# EMG_SS19_Version.net
KiCad netlist of a schematic drawn in EAGLE
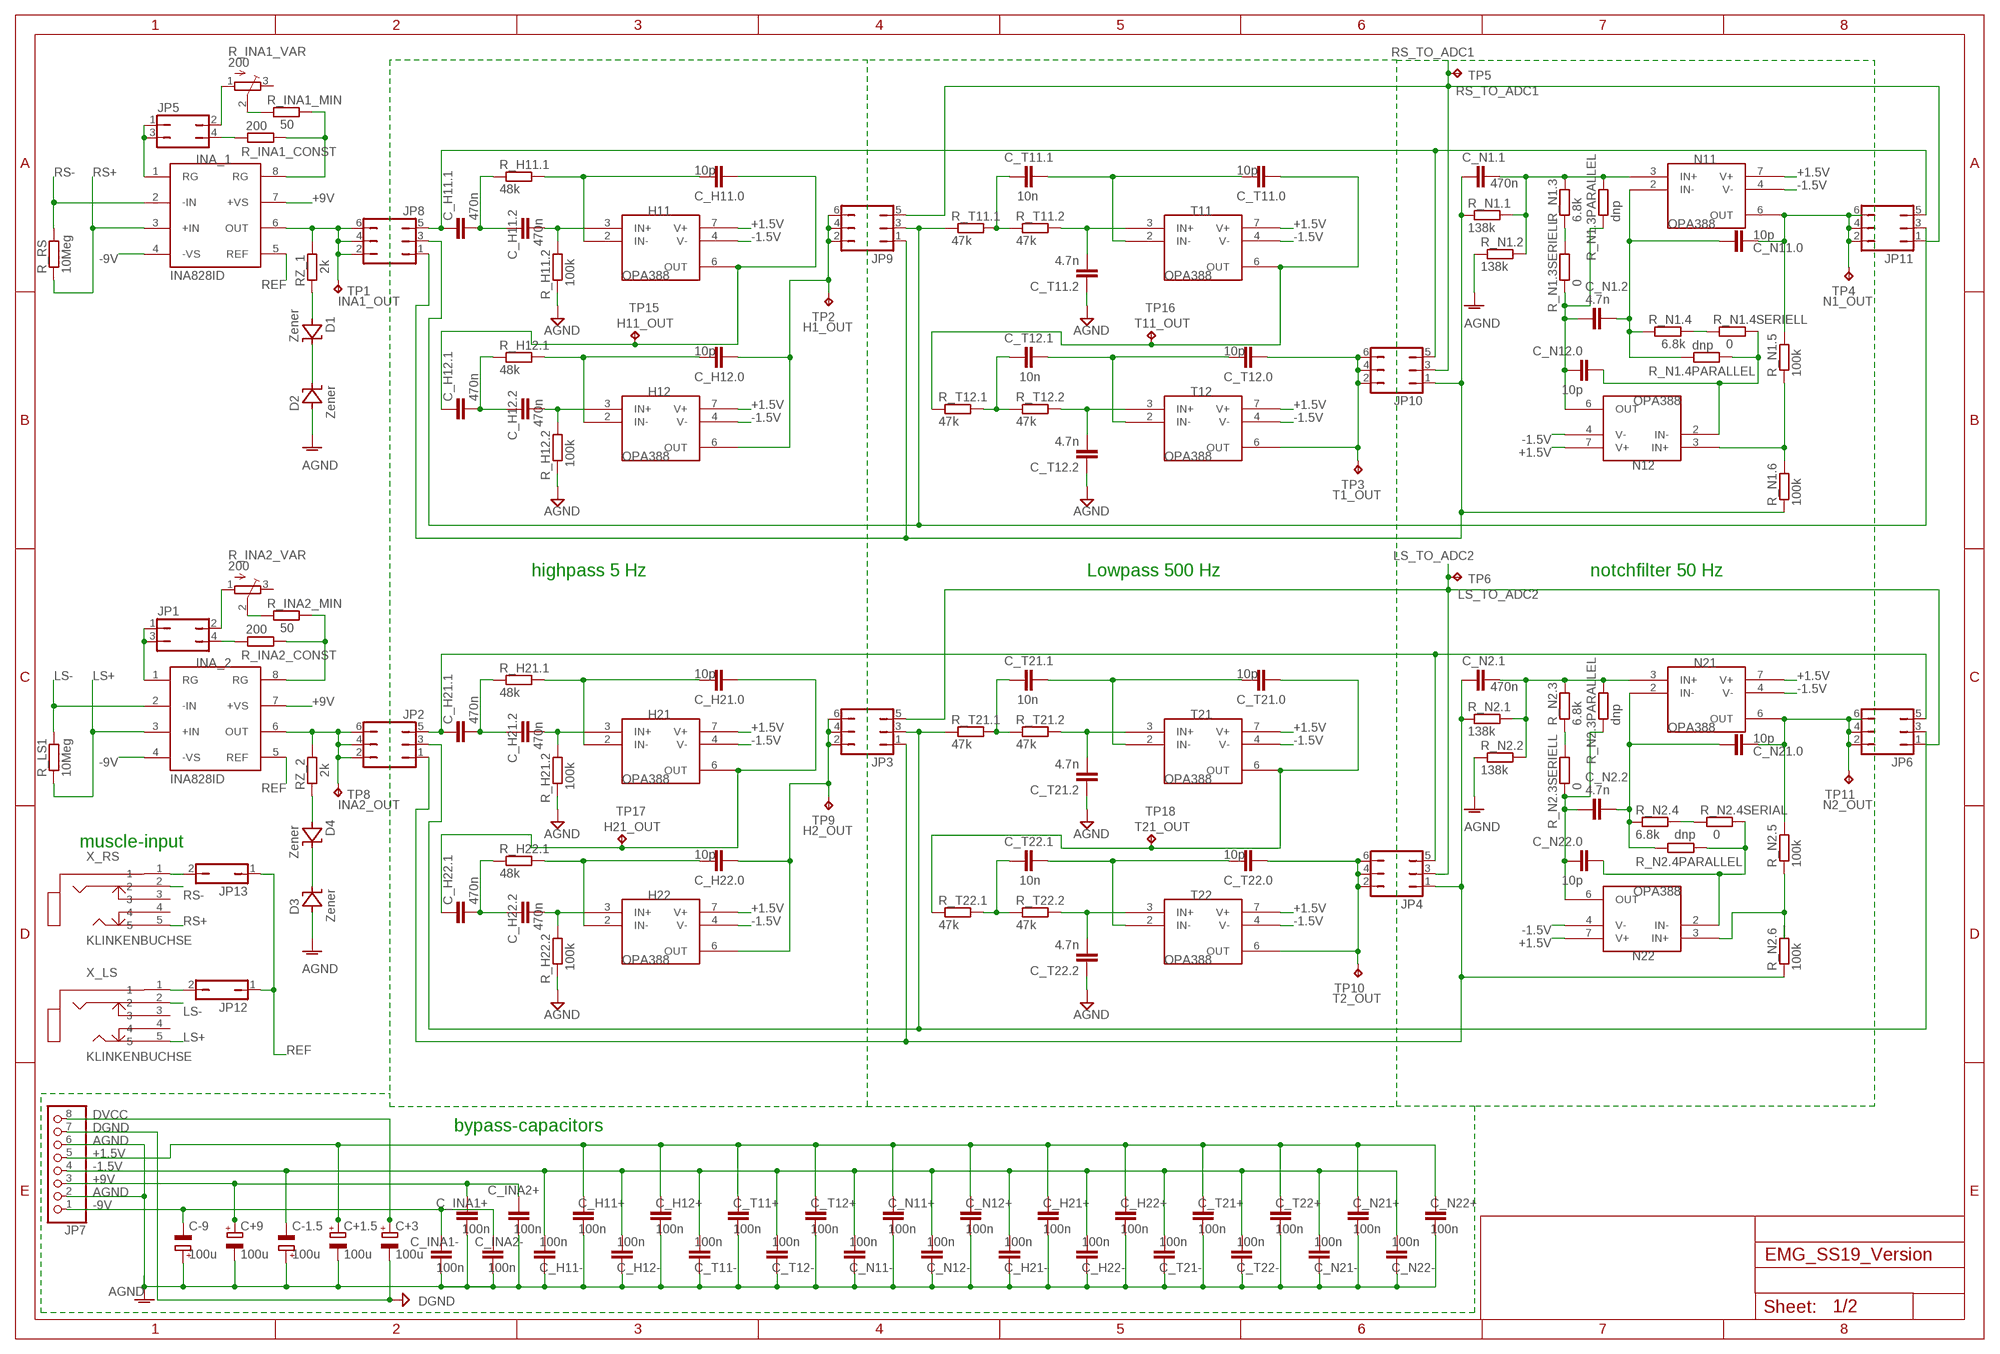
[diagram p0: schematic, sheet 1]
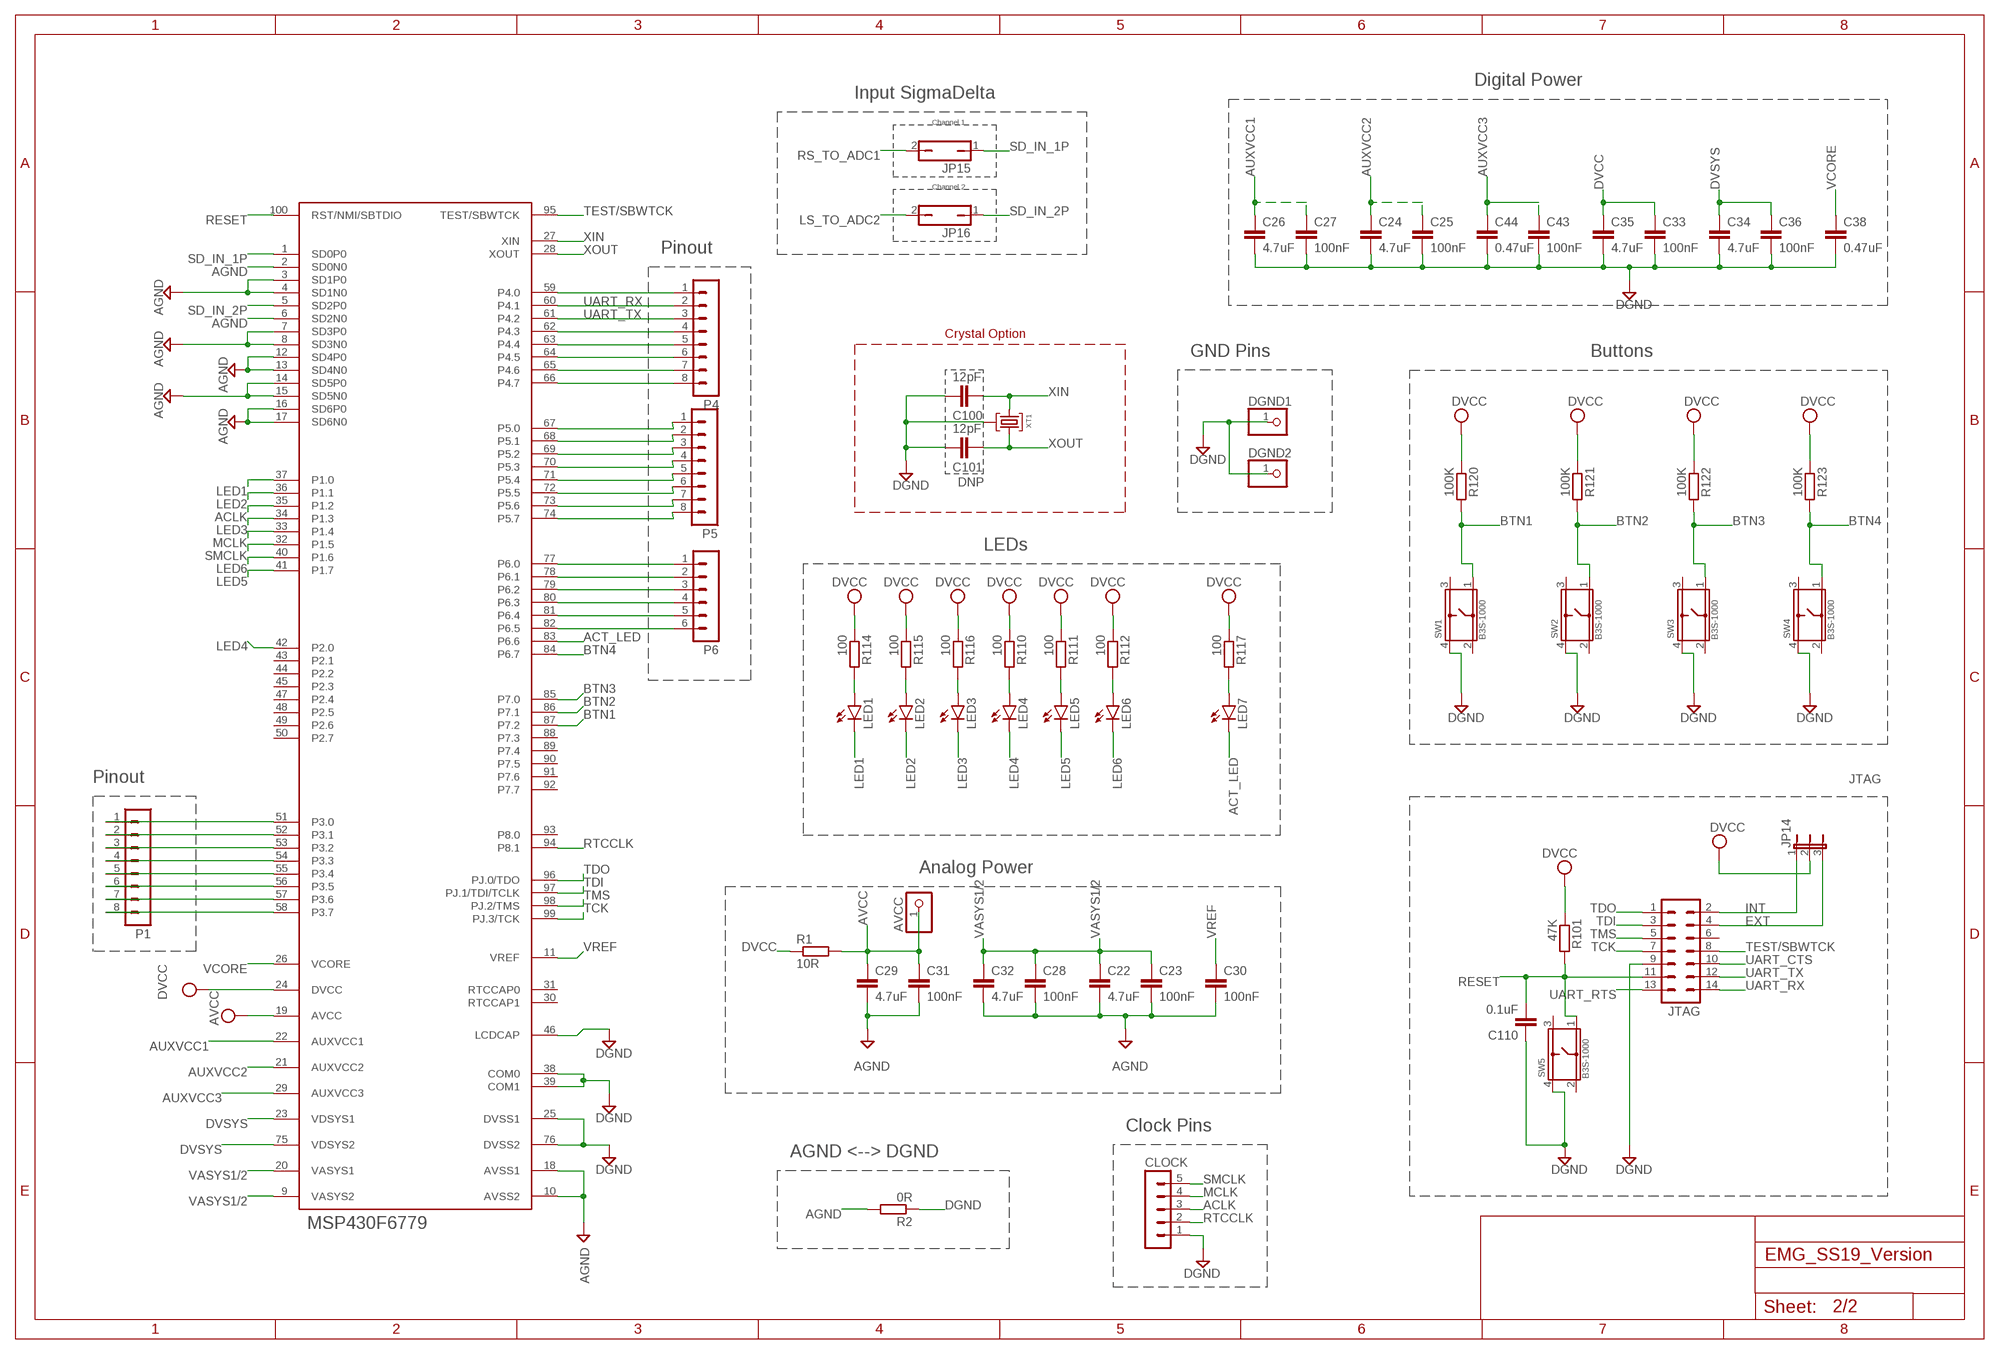
[diagram p1: schematic, sheet 2]

(export (version "E")
  (design (tool "Eeschema 10.0.6"))
  (components
    (comp (ref "C+1.5")
      (value "100u")
      (footprint "eagle-import:RADIAL_SMD_ELKO_6_3")
      (fields (field (name "MF") "Wurth Electronics") (field (name "MP") "865080545012"))
      (libsource (lib "eagle-import") (part "ELKO_SMD"))
    )
    (comp (ref "C+3")
      (value "100u")
      (footprint "eagle-import:RADIAL_SMD_ELKO_6_3")
      (fields (field (name "MF") "Wurth Electronics") (field (name "MP") "865080545012"))
      (libsource (lib "eagle-import") (part "ELKO_SMD"))
    )
    (comp (ref "C+9")
      (value "100u")
      (footprint "eagle-import:RADIAL_SMD_ELKO_6_3")
      (fields (field (name "MF") "Wurth Electronics") (field (name "MP") "865080545012"))
      (libsource (lib "eagle-import") (part "ELKO_SMD"))
    )
    (comp (ref "C-1.5")
      (value "100u")
      (footprint "eagle-import:RADIAL_SMD_ELKO_6_3")
      (fields (field (name "MF") "Wurth Electronics") (field (name "MP") "865080545012"))
      (libsource (lib "eagle-import") (part "ELKO_SMD"))
    )
    (comp (ref "C-9")
      (value "100u")
      (footprint "eagle-import:RADIAL_SMD_ELKO_6_3")
      (fields (field (name "MF") "Wurth Electronics") (field (name "MP") "865080545012"))
      (libsource (lib "eagle-import") (part "ELKO_SMD"))
    )
    (comp (ref "C_H11+")
      (value "100n")
      (footprint "eagle-import:C0805")
      (libsource (lib "eagle-import") (part "C-EUC0805"))
    )
    (comp (ref "C_H11-")
      (value "100n")
      (footprint "eagle-import:C0805")
      (libsource (lib "eagle-import") (part "C-EUC0805"))
    )
    (comp (ref "C_H11.0")
      (value "10p")
      (footprint "eagle-import:C0805")
      (libsource (lib "eagle-import") (part "C-EUC0805"))
    )
    (comp (ref "C_H11.1")
      (value "470n")
      (footprint "eagle-import:C0805")
      (libsource (lib "eagle-import") (part "C-EUC0805"))
    )
    (comp (ref "C_H11.2")
      (value "470n")
      (footprint "eagle-import:C0805")
      (libsource (lib "eagle-import") (part "C-EUC0805"))
    )
    (comp (ref "C_H12+")
      (value "100n")
      (footprint "eagle-import:C0805")
      (libsource (lib "eagle-import") (part "C-EUC0805"))
    )
    (comp (ref "C_H12-")
      (value "100n")
      (footprint "eagle-import:C0805")
      (libsource (lib "eagle-import") (part "C-EUC0805"))
    )
    (comp (ref "C_H12.0")
      (value "10p")
      (footprint "eagle-import:C0805")
      (libsource (lib "eagle-import") (part "C-EUC0805"))
    )
    (comp (ref "C_H12.1")
      (value "470n")
      (footprint "eagle-import:C0805")
      (libsource (lib "eagle-import") (part "C-EUC0805"))
    )
    (comp (ref "C_H12.2")
      (value "470n")
      (footprint "eagle-import:C0805")
      (libsource (lib "eagle-import") (part "C-EUC0805"))
    )
    (comp (ref "C_H21+")
      (value "100n")
      (footprint "eagle-import:C0805")
      (libsource (lib "eagle-import") (part "C-EUC0805"))
    )
    (comp (ref "C_H21-")
      (value "100n")
      (footprint "eagle-import:C0805")
      (libsource (lib "eagle-import") (part "C-EUC0805"))
    )
    (comp (ref "C_H21.0")
      (value "10p")
      (footprint "eagle-import:C0805")
      (libsource (lib "eagle-import") (part "C-EUC0805"))
    )
    (comp (ref "C_H21.1")
      (value "470n")
      (footprint "eagle-import:C0805")
      (libsource (lib "eagle-import") (part "C-EUC0805"))
    )
    (comp (ref "C_H21.2")
      (value "470n")
      (footprint "eagle-import:C0805")
      (libsource (lib "eagle-import") (part "C-EUC0805"))
    )
    (comp (ref "C_H22+")
      (value "100n")
      (footprint "eagle-import:C0805")
      (libsource (lib "eagle-import") (part "C-EUC0805"))
    )
    (comp (ref "C_H22-")
      (value "100n")
      (footprint "eagle-import:C0805")
      (libsource (lib "eagle-import") (part "C-EUC0805"))
    )
    (comp (ref "C_H22.0")
      (value "10p")
      (footprint "eagle-import:C0805")
      (libsource (lib "eagle-import") (part "C-EUC0805"))
    )
    (comp (ref "C_H22.1")
      (value "470n")
      (footprint "eagle-import:C0805")
      (libsource (lib "eagle-import") (part "C-EUC0805"))
    )
    (comp (ref "C_H22.2")
      (value "470n")
      (footprint "eagle-import:C0805")
      (libsource (lib "eagle-import") (part "C-EUC0805"))
    )
    (comp (ref "C_INA1+")
      (value "100n")
      (footprint "eagle-import:C0805")
      (libsource (lib "eagle-import") (part "C-EUC0805"))
    )
    (comp (ref "C_INA1-")
      (value "100n")
      (footprint "eagle-import:C0805")
      (libsource (lib "eagle-import") (part "C-EUC0805"))
    )
    (comp (ref "C_INA2+")
      (value "100n")
      (footprint "eagle-import:C0805")
      (libsource (lib "eagle-import") (part "C-EUC0805"))
    )
    (comp (ref "C_INA2-")
      (value "100n")
      (footprint "eagle-import:C0805")
      (libsource (lib "eagle-import") (part "C-EUC0805"))
    )
    (comp (ref "C_N1.1")
      (value "470n")
      (footprint "eagle-import:C0805")
      (libsource (lib "eagle-import") (part "C-EUC0805"))
    )
    (comp (ref "C_N1.2")
      (value "4.7n")
      (footprint "eagle-import:C0805")
      (libsource (lib "eagle-import") (part "C-EUC0805"))
    )
    (comp (ref "C_N2.1")
      (value "470n")
      (footprint "eagle-import:C0805")
      (libsource (lib "eagle-import") (part "C-EUC0805"))
    )
    (comp (ref "C_N2.2")
      (value "4.7n")
      (footprint "eagle-import:C0805")
      (libsource (lib "eagle-import") (part "C-EUC0805"))
    )
    (comp (ref "C_N11+")
      (value "100n")
      (footprint "eagle-import:C0805")
      (libsource (lib "eagle-import") (part "C-EUC0805"))
    )
    (comp (ref "C_N11-")
      (value "100n")
      (footprint "eagle-import:C0805")
      (libsource (lib "eagle-import") (part "C-EUC0805"))
    )
    (comp (ref "C_N11.0")
      (value "10p")
      (footprint "eagle-import:C0805")
      (libsource (lib "eagle-import") (part "C-EUC0805"))
    )
    (comp (ref "C_N12+")
      (value "100n")
      (footprint "eagle-import:C0805")
      (libsource (lib "eagle-import") (part "C-EUC0805"))
    )
    (comp (ref "C_N12-")
      (value "100n")
      (footprint "eagle-import:C0805")
      (libsource (lib "eagle-import") (part "C-EUC0805"))
    )
    (comp (ref "C_N12.0")
      (value "10p")
      (footprint "eagle-import:C0805")
      (libsource (lib "eagle-import") (part "C-EUC0805"))
    )
    (comp (ref "C_N21+")
      (value "100n")
      (footprint "eagle-import:C0805")
      (libsource (lib "eagle-import") (part "C-EUC0805"))
    )
    (comp (ref "C_N21-")
      (value "100n")
      (footprint "eagle-import:C0805")
      (libsource (lib "eagle-import") (part "C-EUC0805"))
    )
    (comp (ref "C_N21.0")
      (value "10p")
      (footprint "eagle-import:C0805")
      (libsource (lib "eagle-import") (part "C-EUC0805"))
    )
    (comp (ref "C_N22+")
      (value "100n")
      (footprint "eagle-import:C0805")
      (libsource (lib "eagle-import") (part "C-EUC0805"))
    )
    (comp (ref "C_N22-")
      (value "100n")
      (footprint "eagle-import:C0805")
      (libsource (lib "eagle-import") (part "C-EUC0805"))
    )
    (comp (ref "C_N22.0")
      (value "10p")
      (footprint "eagle-import:C0805")
      (libsource (lib "eagle-import") (part "C-EUC0805"))
    )
    (comp (ref "C_T11+")
      (value "100n")
      (footprint "eagle-import:C0805")
      (libsource (lib "eagle-import") (part "C-EUC0805"))
    )
    (comp (ref "C_T11-")
      (value "100n")
      (footprint "eagle-import:C0805")
      (libsource (lib "eagle-import") (part "C-EUC0805"))
    )
    (comp (ref "C_T11.0")
      (value "10p")
      (footprint "eagle-import:C0805")
      (libsource (lib "eagle-import") (part "C-EUC0805"))
    )
    (comp (ref "C_T11.1")
      (value "10n")
      (footprint "eagle-import:C0805")
      (libsource (lib "eagle-import") (part "C-EUC0805"))
    )
    (comp (ref "C_T11.2")
      (value "4.7n")
      (footprint "eagle-import:C0805")
      (libsource (lib "eagle-import") (part "C-EUC0805"))
    )
    (comp (ref "C_T12+")
      (value "100n")
      (footprint "eagle-import:C0805")
      (libsource (lib "eagle-import") (part "C-EUC0805"))
    )
    (comp (ref "C_T12-")
      (value "100n")
      (footprint "eagle-import:C0805")
      (libsource (lib "eagle-import") (part "C-EUC0805"))
    )
    (comp (ref "C_T12.0")
      (value "10p")
      (footprint "eagle-import:C0805")
      (libsource (lib "eagle-import") (part "C-EUC0805"))
    )
    (comp (ref "C_T12.1")
      (value "10n")
      (footprint "eagle-import:C0805")
      (libsource (lib "eagle-import") (part "C-EUC0805"))
    )
    (comp (ref "C_T12.2")
      (value "4.7n")
      (footprint "eagle-import:C0805")
      (libsource (lib "eagle-import") (part "C-EUC0805"))
    )
    (comp (ref "C_T21+")
      (value "100n")
      (footprint "eagle-import:C0805")
      (libsource (lib "eagle-import") (part "C-EUC0805"))
    )
    (comp (ref "C_T21-")
      (value "100n")
      (footprint "eagle-import:C0805")
      (libsource (lib "eagle-import") (part "C-EUC0805"))
    )
    (comp (ref "C_T21.0")
      (value "10p")
      (footprint "eagle-import:C0805")
      (libsource (lib "eagle-import") (part "C-EUC0805"))
    )
    (comp (ref "C_T21.1")
      (value "10n")
      (footprint "eagle-import:C0805")
      (libsource (lib "eagle-import") (part "C-EUC0805"))
    )
    (comp (ref "C_T21.2")
      (value "4.7n")
      (footprint "eagle-import:C0805")
      (libsource (lib "eagle-import") (part "C-EUC0805"))
    )
    (comp (ref "C_T22+")
      (value "100n")
      (footprint "eagle-import:C0805")
      (libsource (lib "eagle-import") (part "C-EUC0805"))
    )
    (comp (ref "C_T22-")
      (value "100n")
      (footprint "eagle-import:C0805")
      (libsource (lib "eagle-import") (part "C-EUC0805"))
    )
    (comp (ref "C_T22.0")
      (value "10p")
      (footprint "eagle-import:C0805")
      (libsource (lib "eagle-import") (part "C-EUC0805"))
    )
    (comp (ref "C_T22.1")
      (value "10n")
      (footprint "eagle-import:C0805")
      (libsource (lib "eagle-import") (part "C-EUC0805"))
    )
    (comp (ref "C_T22.2")
      (value "4.7n")
      (footprint "eagle-import:C0805")
      (libsource (lib "eagle-import") (part "C-EUC0805"))
    )
    (comp (ref "D1")
      (value "Zener")
      (footprint "eagle-import:SOT-23")
      (fields (field (name "MF") "Diodes Inc.") (field (name "MP") "ZXCT1109SA-7"))
      (libsource (lib "eagle-import") (part "ZENER_SMD_ZD_8.2"))
    )
    (comp (ref "D2")
      (value "Zener")
      (footprint "eagle-import:SOT-23")
      (fields (field (name "MF") "Diodes Inc.") (field (name "MP") "ZXCT1109SA-7"))
      (libsource (lib "eagle-import") (part "ZENER_SMD_ZD_8.2"))
    )
    (comp (ref "D3")
      (value "Zener")
      (footprint "eagle-import:SOT-23")
      (fields (field (name "MF") "Diodes Inc.") (field (name "MP") "ZXCT1109SA-7"))
      (libsource (lib "eagle-import") (part "ZENER_SMD_ZD_8.2"))
    )
    (comp (ref "D4")
      (value "Zener")
      (footprint "eagle-import:SOT-23")
      (fields (field (name "MF") "Diodes Inc.") (field (name "MP") "ZXCT1109SA-7"))
      (libsource (lib "eagle-import") (part "ZENER_SMD_ZD_8.2"))
    )
    (comp (ref "H11")
      (value "OPA388")
      (footprint "eagle-import:SOIC127P600X175-8N")
      (libsource (lib "eagle-import") (part "OPA388"))
    )
    (comp (ref "H12")
      (value "OPA388")
      (footprint "eagle-import:SOIC127P600X175-8N")
      (libsource (lib "eagle-import") (part "OPA388"))
    )
    (comp (ref "H21")
      (value "OPA388")
      (footprint "eagle-import:SOIC127P600X175-8N")
      (libsource (lib "eagle-import") (part "OPA388"))
    )
    (comp (ref "H22")
      (value "OPA388")
      (footprint "eagle-import:SOIC127P600X175-8N")
      (libsource (lib "eagle-import") (part "OPA388"))
    )
    (comp (ref "INA_1")
      (value "INA828ID")
      (footprint "eagle-import:SOIC8")
      (fields (field (name "DIGI-KEY_PART_NUMBER") "296-47415-ND") (field (name "MF") "Texas Instruments"))
      (libsource (lib "eagle-import") (part "INA828ID"))
    )
    (comp (ref "INA_2")
      (value "INA828ID")
      (footprint "eagle-import:SOIC8")
      (fields (field (name "DIGI-KEY_PART_NUMBER") "296-47415-ND") (field (name "MF") "Texas Instruments"))
      (libsource (lib "eagle-import") (part "INA828ID"))
    )
    (comp (ref "JP1")
      (value "JP2Q")
      (footprint "eagle-import:JP2Q")
      (libsource (lib "eagle-import") (part "JP2Q"))
    )
    (comp (ref "JP2")
      (value "JP3Q")
      (footprint "eagle-import:JP3Q")
      (libsource (lib "eagle-import") (part "JP3Q"))
    )
    (comp (ref "JP3")
      (value "JP3Q")
      (footprint "eagle-import:JP3Q")
      (libsource (lib "eagle-import") (part "JP3Q"))
    )
    (comp (ref "JP4")
      (value "JP3Q")
      (footprint "eagle-import:JP3Q")
      (libsource (lib "eagle-import") (part "JP3Q"))
    )
    (comp (ref "JP5")
      (value "JP2Q")
      (footprint "eagle-import:JP2Q")
      (libsource (lib "eagle-import") (part "JP2Q"))
    )
    (comp (ref "JP6")
      (value "JP3Q")
      (footprint "eagle-import:JP3Q")
      (libsource (lib "eagle-import") (part "JP3Q"))
    )
    (comp (ref "JP7")
      (value "PINHD-1X8")
      (footprint "eagle-import:1X08")
      (libsource (lib "eagle-import") (part "PINHD-1X8"))
    )
    (comp (ref "JP8")
      (value "JP3Q")
      (footprint "eagle-import:JP3Q")
      (libsource (lib "eagle-import") (part "JP3Q"))
    )
    (comp (ref "JP9")
      (value "JP3Q")
      (footprint "eagle-import:JP3Q")
      (libsource (lib "eagle-import") (part "JP3Q"))
    )
    (comp (ref "JP10")
      (value "JP3Q")
      (footprint "eagle-import:JP3Q")
      (libsource (lib "eagle-import") (part "JP3Q"))
    )
    (comp (ref "JP11")
      (value "JP3Q")
      (footprint "eagle-import:JP3Q")
      (libsource (lib "eagle-import") (part "JP3Q"))
    )
    (comp (ref "JP12")
      (value "JP1Q")
      (footprint "eagle-import:JP1")
      (libsource (lib "eagle-import") (part "JP1Q"))
    )
    (comp (ref "JP13")
      (value "JP1Q")
      (footprint "eagle-import:JP1")
      (libsource (lib "eagle-import") (part "JP1Q"))
    )
    (comp (ref "N11")
      (value "OPA388")
      (footprint "eagle-import:SOIC127P600X175-8N")
      (libsource (lib "eagle-import") (part "OPA388"))
    )
    (comp (ref "N12")
      (value "OPA388")
      (footprint "eagle-import:SOIC127P600X175-8N")
      (libsource (lib "eagle-import") (part "OPA388"))
    )
    (comp (ref "N21")
      (value "OPA388")
      (footprint "eagle-import:SOIC127P600X175-8N")
      (libsource (lib "eagle-import") (part "OPA388"))
    )
    (comp (ref "N22")
      (value "OPA388")
      (footprint "eagle-import:SOIC127P600X175-8N")
      (libsource (lib "eagle-import") (part "OPA388"))
    )
    (comp (ref "RZ_1")
      (value "2k")
      (footprint "eagle-import:R0805")
      (libsource (lib "eagle-import") (part "R-EU_R0805"))
    )
    (comp (ref "RZ_2")
      (value "2k")
      (footprint "eagle-import:R0805")
      (libsource (lib "eagle-import") (part "R-EU_R0805"))
    )
    (comp (ref "R_H11.1")
      (value "48k")
      (footprint "eagle-import:R0805")
      (libsource (lib "eagle-import") (part "R-EU_R0805"))
    )
    (comp (ref "R_H11.2")
      (value "100k")
      (footprint "eagle-import:R0805")
      (libsource (lib "eagle-import") (part "R-EU_R0805"))
    )
    (comp (ref "R_H12.1")
      (value "48k")
      (footprint "eagle-import:R0805")
      (libsource (lib "eagle-import") (part "R-EU_R0805"))
    )
    (comp (ref "R_H12.2")
      (value "100k")
      (footprint "eagle-import:R0805")
      (libsource (lib "eagle-import") (part "R-EU_R0805"))
    )
    (comp (ref "R_H21.1")
      (value "48k")
      (footprint "eagle-import:R0805")
      (libsource (lib "eagle-import") (part "R-EU_R0805"))
    )
    (comp (ref "R_H21.2")
      (value "100k")
      (footprint "eagle-import:R0805")
      (libsource (lib "eagle-import") (part "R-EU_R0805"))
    )
    (comp (ref "R_H22.1")
      (value "48k")
      (footprint "eagle-import:R0805")
      (libsource (lib "eagle-import") (part "R-EU_R0805"))
    )
    (comp (ref "R_H22.2")
      (value "100k")
      (footprint "eagle-import:R0805")
      (libsource (lib "eagle-import") (part "R-EU_R0805"))
    )
    (comp (ref "R_INA1_CONST")
      (value "200")
      (footprint "eagle-import:R0805")
      (libsource (lib "eagle-import") (part "R-EU_R0805"))
    )
    (comp (ref "R_INA1_MIN")
      (value "50")
      (footprint "eagle-import:R0805")
      (libsource (lib "eagle-import") (part "R-EU_R0805"))
    )
    (comp (ref "R_INA1_VAR")
      (value "200")
      (footprint "eagle-import:SM-42_43W")
      (fields (field (name "SPICEPREFIX") "J"))
      (libsource (lib "eagle-import") (part "TRIM_EU-SM-42/43W"))
    )
    (comp (ref "R_INA2_CONST")
      (value "200")
      (footprint "eagle-import:R0805")
      (libsource (lib "eagle-import") (part "R-EU_R0805"))
    )
    (comp (ref "R_INA2_MIN")
      (value "50")
      (footprint "eagle-import:R0805")
      (libsource (lib "eagle-import") (part "R-EU_R0805"))
    )
    (comp (ref "R_INA2_VAR")
      (value "200")
      (footprint "eagle-import:SM-42_43W")
      (fields (field (name "SPICEPREFIX") "J"))
      (libsource (lib "eagle-import") (part "TRIM_EU-SM-42/43W"))
    )
    (comp (ref "R_LS1")
      (value "10Meg")
      (footprint "eagle-import:R0805")
      (libsource (lib "eagle-import") (part "R-EU_R0805"))
    )
    (comp (ref "R_N1.1")
      (value "138k")
      (footprint "eagle-import:R0805")
      (libsource (lib "eagle-import") (part "R-EU_R0805"))
    )
    (comp (ref "R_N1.2")
      (value "138k")
      (footprint "eagle-import:R0805")
      (libsource (lib "eagle-import") (part "R-EU_R0805"))
    )
    (comp (ref "R_N1.3")
      (value "6.8k")
      (footprint "eagle-import:R0805")
      (libsource (lib "eagle-import") (part "R-EU_R0805"))
    )
    (comp (ref "R_N1.3PARALLEL")
      (value "dnp")
      (footprint "eagle-import:R0805")
      (libsource (lib "eagle-import") (part "R-EU_R0805"))
    )
    (comp (ref "R_N1.3SERIELL")
      (value "0")
      (footprint "eagle-import:R0805")
      (libsource (lib "eagle-import") (part "R-EU_R0805"))
    )
    (comp (ref "R_N1.4")
      (value "6.8k")
      (footprint "eagle-import:R0805")
      (libsource (lib "eagle-import") (part "R-EU_R0805"))
    )
    (comp (ref "R_N1.4PARALLEL")
      (value "dnp")
      (footprint "eagle-import:R0805")
      (libsource (lib "eagle-import") (part "R-EU_R0805"))
    )
    (comp (ref "R_N1.4SERIELL")
      (value "0")
      (footprint "eagle-import:R0805")
      (libsource (lib "eagle-import") (part "R-EU_R0805"))
    )
    (comp (ref "R_N1.5")
      (value "100k")
      (footprint "eagle-import:R0805")
      (libsource (lib "eagle-import") (part "R-EU_R0805"))
    )
    (comp (ref "R_N1.6")
      (value "100k")
      (footprint "eagle-import:R0805")
      (libsource (lib "eagle-import") (part "R-EU_R0805"))
    )
    (comp (ref "R_N2.1")
      (value "138k")
      (footprint "eagle-import:R0805")
      (libsource (lib "eagle-import") (part "R-EU_R0805"))
    )
    (comp (ref "R_N2.2")
      (value "138k")
      (footprint "eagle-import:R0805")
      (libsource (lib "eagle-import") (part "R-EU_R0805"))
    )
    (comp (ref "R_N2.3")
      (value "6.8k")
      (footprint "eagle-import:R0805")
      (libsource (lib "eagle-import") (part "R-EU_R0805"))
    )
    (comp (ref "R_N2.3PARALLEL")
      (value "dnp")
      (footprint "eagle-import:R0805")
      (libsource (lib "eagle-import") (part "R-EU_R0805"))
    )
    (comp (ref "R_N2.3SERIELL")
      (value "0")
      (footprint "eagle-import:R0805")
      (libsource (lib "eagle-import") (part "R-EU_R0805"))
    )
    (comp (ref "R_N2.4")
      (value "6.8k")
      (footprint "eagle-import:R0805")
      (libsource (lib "eagle-import") (part "R-EU_R0805"))
    )
    (comp (ref "R_N2.4PARALLEL")
      (value "dnp")
      (footprint "eagle-import:R0805")
      (libsource (lib "eagle-import") (part "R-EU_R0805"))
    )
    (comp (ref "R_N2.4SERIAL")
      (value "0")
      (footprint "eagle-import:R0805")
      (libsource (lib "eagle-import") (part "R-EU_R0805"))
    )
    (comp (ref "R_N2.5")
      (value "100k")
      (footprint "eagle-import:R0805")
      (libsource (lib "eagle-import") (part "R-EU_R0805"))
    )
    (comp (ref "R_N2.6")
      (value "100k")
      (footprint "eagle-import:R0805")
      (libsource (lib "eagle-import") (part "R-EU_R0805"))
    )
    (comp (ref "R_RS")
      (value "10Meg")
      (footprint "eagle-import:R0805")
      (libsource (lib "eagle-import") (part "R-EU_R0805"))
    )
    (comp (ref "R_T11.1")
      (value "47k")
      (footprint "eagle-import:R0805")
      (libsource (lib "eagle-import") (part "R-EU_R0805"))
    )
    (comp (ref "R_T11.2")
      (value "47k")
      (footprint "eagle-import:R0805")
      (libsource (lib "eagle-import") (part "R-EU_R0805"))
    )
    (comp (ref "R_T12.1")
      (value "47k")
      (footprint "eagle-import:R0805")
      (libsource (lib "eagle-import") (part "R-EU_R0805"))
    )
    (comp (ref "R_T12.2")
      (value "47k")
      (footprint "eagle-import:R0805")
      (libsource (lib "eagle-import") (part "R-EU_R0805"))
    )
    (comp (ref "R_T21.1")
      (value "47k")
      (footprint "eagle-import:R0805")
      (libsource (lib "eagle-import") (part "R-EU_R0805"))
    )
    (comp (ref "R_T21.2")
      (value "47k")
      (footprint "eagle-import:R0805")
      (libsource (lib "eagle-import") (part "R-EU_R0805"))
    )
    (comp (ref "R_T22.1")
      (value "47k")
      (footprint "eagle-import:R0805")
      (libsource (lib "eagle-import") (part "R-EU_R0805"))
    )
    (comp (ref "R_T22.2")
      (value "47k")
      (footprint "eagle-import:R0805")
      (libsource (lib "eagle-import") (part "R-EU_R0805"))
    )
    (comp (ref "T11")
      (value "OPA388")
      (footprint "eagle-import:SOIC127P600X175-8N")
      (libsource (lib "eagle-import") (part "OPA388"))
    )
    (comp (ref "T12")
      (value "OPA388")
      (footprint "eagle-import:SOIC127P600X175-8N")
      (libsource (lib "eagle-import") (part "OPA388"))
    )
    (comp (ref "T21")
      (value "OPA388")
      (footprint "eagle-import:SOIC127P600X175-8N")
      (libsource (lib "eagle-import") (part "OPA388"))
    )
    (comp (ref "T22")
      (value "OPA388")
      (footprint "eagle-import:SOIC127P600X175-8N")
      (libsource (lib "eagle-import") (part "OPA388"))
    )
    (comp (ref "TP1")
      (value "TPPAD1-13")
      (footprint "eagle-import:P1-13")
      (libsource (lib "eagle-import") (part "TPPAD1-13"))
    )
    (comp (ref "TP2")
      (value "TPPAD1-13")
      (footprint "eagle-import:P1-13")
      (libsource (lib "eagle-import") (part "TPPAD1-13"))
    )
    (comp (ref "TP3")
      (value "TPPAD1-13")
      (footprint "eagle-import:P1-13")
      (libsource (lib "eagle-import") (part "TPPAD1-13"))
    )
    (comp (ref "TP4")
      (value "TPPAD1-13")
      (footprint "eagle-import:P1-13")
      (libsource (lib "eagle-import") (part "TPPAD1-13"))
    )
    (comp (ref "TP5")
      (value "RS_TO_ADC")
      (footprint "eagle-import:P1-13")
      (libsource (lib "eagle-import") (part "TPPAD1-13"))
    )
    (comp (ref "TP6")
      (value "LS_TO_ADC")
      (footprint "eagle-import:P1-13")
      (libsource (lib "eagle-import") (part "TPPAD1-13"))
    )
    (comp (ref "TP8")
      (value "TPPAD1-13")
      (footprint "eagle-import:P1-13")
      (libsource (lib "eagle-import") (part "TPPAD1-13"))
    )
    (comp (ref "TP9")
      (value "TPPAD1-13")
      (footprint "eagle-import:P1-13")
      (libsource (lib "eagle-import") (part "TPPAD1-13"))
    )
    (comp (ref "TP10")
      (value "TPPAD1-13")
      (footprint "eagle-import:P1-13")
      (libsource (lib "eagle-import") (part "TPPAD1-13"))
    )
    (comp (ref "TP11")
      (value "TPPAD1-13")
      (footprint "eagle-import:P1-13")
      (libsource (lib "eagle-import") (part "TPPAD1-13"))
    )
    (comp (ref "TP15")
      (value "TPPAD1-13")
      (footprint "eagle-import:P1-13")
      (libsource (lib "eagle-import") (part "TPPAD1-13"))
    )
    (comp (ref "TP16")
      (value "TPPAD1-13")
      (footprint "eagle-import:P1-13")
      (libsource (lib "eagle-import") (part "TPPAD1-13"))
    )
    (comp (ref "TP17")
      (value "TPPAD1-13")
      (footprint "eagle-import:P1-13")
      (libsource (lib "eagle-import") (part "TPPAD1-13"))
    )
    (comp (ref "TP18")
      (value "TPPAD1-13")
      (footprint "eagle-import:P1-13")
      (libsource (lib "eagle-import") (part "TPPAD1-13"))
    )
    (comp (ref "X_LS")
      (value "KLINKENBUCHSE")
      (footprint "eagle-import:FC68131-5P")
      (fields (field (name "MF") "Cliff") (field (name "MP") "FC68131"))
      (libsource (lib "eagle-import") (part "KLINKENBUCHSE"))
    )
    (comp (ref "X_RS")
      (value "KLINKENBUCHSE")
      (footprint "eagle-import:FC68131-5P")
      (fields (field (name "MF") "Cliff") (field (name "MP") "FC68131"))
      (libsource (lib "eagle-import") (part "KLINKENBUCHSE"))
    )
    (comp (ref "AVCC")
      (value "PINHD-1X1")
      (footprint "eagle-import:1X01")
      (libsource (lib "eagle-import") (part "PINHD-1X1"))
    )
    (comp (ref "C22")
      (value "4.7uF")
      (footprint "eagle-import:C0805")
      (libsource (lib "eagle-import") (part "resistor_C-EUC0805"))
    )
    (comp (ref "C23")
      (value "100nF")
      (footprint "eagle-import:C0805")
      (libsource (lib "eagle-import") (part "resistor_C-EUC0805"))
    )
    (comp (ref "C24")
      (value "4.7uF")
      (footprint "eagle-import:C0805")
      (libsource (lib "eagle-import") (part "resistor_C-EUC0805"))
    )
    (comp (ref "C25")
      (value "100nF")
      (footprint "eagle-import:C0805")
      (libsource (lib "eagle-import") (part "resistor_C-EUC0805"))
    )
    (comp (ref "C26")
      (value "4.7uF")
      (footprint "eagle-import:C0805")
      (libsource (lib "eagle-import") (part "resistor_C-EUC0805"))
    )
    (comp (ref "C27")
      (value "100nF")
      (footprint "eagle-import:C0805")
      (libsource (lib "eagle-import") (part "resistor_C-EUC0805"))
    )
    (comp (ref "C28")
      (value "100nF")
      (footprint "eagle-import:C0805")
      (libsource (lib "eagle-import") (part "resistor_C-EUC0805"))
    )
    (comp (ref "C29")
      (value "4.7uF")
      (footprint "eagle-import:C0805")
      (libsource (lib "eagle-import") (part "resistor_C-EUC0805"))
    )
    (comp (ref "C30")
      (value "100nF")
      (footprint "eagle-import:C0805")
      (libsource (lib "eagle-import") (part "resistor_C-EUC0805"))
    )
    (comp (ref "C31")
      (value "100nF")
      (footprint "eagle-import:C0805")
      (libsource (lib "eagle-import") (part "resistor_C-EUC0805"))
    )
    (comp (ref "C32")
      (value "4.7uF")
      (footprint "eagle-import:C0805")
      (libsource (lib "eagle-import") (part "resistor_C-EUC0805"))
    )
    (comp (ref "C33")
      (value "100nF")
      (footprint "eagle-import:C0805")
      (libsource (lib "eagle-import") (part "resistor_C-EUC0805"))
    )
    (comp (ref "C34")
      (value "4.7uF")
      (footprint "eagle-import:C0805")
      (libsource (lib "eagle-import") (part "resistor_C-EUC0805"))
    )
    (comp (ref "C35")
      (value "4.7uF")
      (footprint "eagle-import:C0805")
      (libsource (lib "eagle-import") (part "resistor_C-EUC0805"))
    )
    (comp (ref "C36")
      (value "100nF")
      (footprint "eagle-import:C0805")
      (libsource (lib "eagle-import") (part "resistor_C-EUC0805"))
    )
    (comp (ref "C38")
      (value "0.47uF")
      (footprint "eagle-import:C0805")
      (libsource (lib "eagle-import") (part "resistor_C-EUC0805"))
    )
    (comp (ref "C43")
      (value "100nF")
      (footprint "eagle-import:C0805")
      (libsource (lib "eagle-import") (part "resistor_C-EUC0805"))
    )
    (comp (ref "C44")
      (value "0.47uF")
      (footprint "eagle-import:C0805")
      (libsource (lib "eagle-import") (part "resistor_C-EUC0805"))
    )
    (comp (ref "C100")
      (value "12pF")
      (footprint "eagle-import:C0805")
      (libsource (lib "eagle-import") (part "resistor_C-EUC0805"))
    )
    (comp (ref "C101")
      (value "12pF")
      (footprint "eagle-import:C0805")
      (libsource (lib "eagle-import") (part "resistor_C-EUC0805"))
    )
    (comp (ref "C110")
      (value "0.1uF")
      (footprint "eagle-import:C0805")
      (libsource (lib "eagle-import") (part "resistor_C-EUC0805"))
    )
    (comp (ref "CLOCK")
      (value "MA05-1")
      (footprint "eagle-import:MA05-1")
      (libsource (lib "eagle-import") (part "MA05-1"))
    )
    (comp (ref "DGND1")
      (value "PINHD-1X1")
      (footprint "eagle-import:1X01")
      (libsource (lib "eagle-import") (part "PINHD-1X1"))
    )
    (comp (ref "DGND2")
      (value "PINHD-1X1")
      (footprint "eagle-import:1X01")
      (libsource (lib "eagle-import") (part "PINHD-1X1"))
    )
    (comp (ref "JP14")
      (value "JP2E")
      (footprint "eagle-import:JP2")
      (libsource (lib "eagle-import") (part "JP2E"))
    )
    (comp (ref "JP15")
      (value "JP1Q")
      (footprint "eagle-import:JP1")
      (libsource (lib "eagle-import") (part "JP1Q"))
    )
    (comp (ref "JP16")
      (value "JP1Q")
      (footprint "eagle-import:JP1")
      (libsource (lib "eagle-import") (part "JP1Q"))
    )
    (comp (ref "JTAG")
      (value "ML14")
      (footprint "eagle-import:ML14")
      (libsource (lib "eagle-import") (part "ML14"))
    )
    (comp (ref "LED1")
      (value "LEDCHIP-LED0805")
      (footprint "eagle-import:CHIP-LED0805")
      (libsource (lib "eagle-import") (part "LEDCHIP-LED0805"))
    )
    (comp (ref "LED2")
      (value "LEDCHIP-LED0805")
      (footprint "eagle-import:CHIP-LED0805")
      (libsource (lib "eagle-import") (part "LEDCHIP-LED0805"))
    )
    (comp (ref "LED3")
      (value "LEDCHIP-LED0805")
      (footprint "eagle-import:CHIP-LED0805")
      (libsource (lib "eagle-import") (part "LEDCHIP-LED0805"))
    )
    (comp (ref "LED4")
      (value "LEDCHIP-LED0805")
      (footprint "eagle-import:CHIP-LED0805")
      (libsource (lib "eagle-import") (part "LEDCHIP-LED0805"))
    )
    (comp (ref "LED5")
      (value "LEDCHIP-LED0805")
      (footprint "eagle-import:CHIP-LED0805")
      (libsource (lib "eagle-import") (part "LEDCHIP-LED0805"))
    )
    (comp (ref "LED6")
      (value "LEDCHIP-LED0805")
      (footprint "eagle-import:CHIP-LED0805")
      (libsource (lib "eagle-import") (part "LEDCHIP-LED0805"))
    )
    (comp (ref "LED7")
      (value "LEDCHIP-LED0805")
      (footprint "eagle-import:CHIP-LED0805")
      (libsource (lib "eagle-import") (part "LEDCHIP-LED0805"))
    )
    (comp (ref "P1")
      (value "MA08-1")
      (footprint "eagle-import:MA08-1")
      (libsource (lib "eagle-import") (part "MA08-1"))
    )
    (comp (ref "P4")
      (value "MA08-1")
      (footprint "eagle-import:MA08-1")
      (libsource (lib "eagle-import") (part "MA08-1"))
    )
    (comp (ref "P5")
      (value "MA08-1")
      (footprint "eagle-import:MA08-1")
      (libsource (lib "eagle-import") (part "MA08-1"))
    )
    (comp (ref "P6")
      (value "MA06-1")
      (footprint "eagle-import:MA06-1")
      (libsource (lib "eagle-import") (part "MA06-1"))
    )
    (comp (ref "R1")
      (value "10R")
      (footprint "eagle-import:R0805")
      (libsource (lib "eagle-import") (part "resistor_R-EU_R0805"))
    )
    (comp (ref "R2")
      (value "0R")
      (footprint "eagle-import:R0805")
      (libsource (lib "eagle-import") (part "resistor_R-EU_R0805"))
    )
    (comp (ref "R101")
      (value "47K")
      (footprint "eagle-import:R0805")
      (libsource (lib "eagle-import") (part "resistor_R-EU_R0805"))
    )
    (comp (ref "R110")
      (value "100")
      (footprint "eagle-import:R0805")
      (libsource (lib "eagle-import") (part "resistor_R-EU_R0805"))
    )
    (comp (ref "R111")
      (value "100")
      (footprint "eagle-import:R0805")
      (libsource (lib "eagle-import") (part "resistor_R-EU_R0805"))
    )
    (comp (ref "R112")
      (value "100")
      (footprint "eagle-import:R0805")
      (libsource (lib "eagle-import") (part "resistor_R-EU_R0805"))
    )
    (comp (ref "R114")
      (value "100")
      (footprint "eagle-import:R0805")
      (libsource (lib "eagle-import") (part "resistor_R-EU_R0805"))
    )
    (comp (ref "R115")
      (value "100")
      (footprint "eagle-import:R0805")
      (libsource (lib "eagle-import") (part "resistor_R-EU_R0805"))
    )
    (comp (ref "R116")
      (value "100")
      (footprint "eagle-import:R0805")
      (libsource (lib "eagle-import") (part "resistor_R-EU_R0805"))
    )
    (comp (ref "R117")
      (value "100")
      (footprint "eagle-import:R0805")
      (libsource (lib "eagle-import") (part "resistor_R-EU_R0805"))
    )
    (comp (ref "R120")
      (value "100K")
      (footprint "eagle-import:R0805")
      (libsource (lib "eagle-import") (part "resistor_R-EU_R0805"))
    )
    (comp (ref "R121")
      (value "100K")
      (footprint "eagle-import:R0805")
      (libsource (lib "eagle-import") (part "resistor_R-EU_R0805"))
    )
    (comp (ref "R122")
      (value "100K")
      (footprint "eagle-import:R0805")
      (libsource (lib "eagle-import") (part "resistor_R-EU_R0805"))
    )
    (comp (ref "R123")
      (value "100K")
      (footprint "eagle-import:R0805")
      (libsource (lib "eagle-import") (part "resistor_R-EU_R0805"))
    )
    (comp (ref "SW1")
      (value "B3S-1000")
      (footprint "eagle-import:SW_B3S-1000")
      (fields (field (name "MF") "Omron"))
      (libsource (lib "eagle-import") (part "B3S-1000"))
    )
    (comp (ref "SW2")
      (value "B3S-1000")
      (footprint "eagle-import:SW_B3S-1000")
      (fields (field (name "MF") "Omron"))
      (libsource (lib "eagle-import") (part "B3S-1000"))
    )
    (comp (ref "SW3")
      (value "B3S-1000")
      (footprint "eagle-import:SW_B3S-1000")
      (fields (field (name "MF") "Omron"))
      (libsource (lib "eagle-import") (part "B3S-1000"))
    )
    (comp (ref "SW4")
      (value "B3S-1000")
      (footprint "eagle-import:SW_B3S-1000")
      (fields (field (name "MF") "Omron"))
      (libsource (lib "eagle-import") (part "B3S-1000"))
    )
    (comp (ref "SW5")
      (value "B3S-1000")
      (footprint "eagle-import:SW_B3S-1000")
      (fields (field (name "MF") "Omron"))
      (libsource (lib "eagle-import") (part "B3S-1000"))
    )
    (comp (ref "U$1")
      (value "MSP430F6779PZ")
      (footprint "eagle-import:S-PQFP-G100(PZ)")
      (libsource (lib "eagle-import") (part "MSP430F6779PZ"))
    )
    (comp (ref "XT1")
      (value "CM200T")
      (footprint "eagle-import:CM200T")
      (libsource (lib "eagle-import") (part "CM200T"))
    )
  )
  (nets
    (net (code "1") (name "+1.5V") (class "Default")
      (node (ref "C+1.5") (pin "+") (pinfunction "+_+") (pintype "passive"))
      (node (ref "C_H11+") (pin "1") (pinfunction "1_1") (pintype "passive"))
      (node (ref "C_H12+") (pin "1") (pinfunction "1_1") (pintype "passive"))
      (node (ref "C_H21+") (pin "1") (pinfunction "1_1") (pintype "passive"))
      (node (ref "C_H22+") (pin "1") (pinfunction "1_1") (pintype "passive"))
      (node (ref "C_N11+") (pin "1") (pinfunction "1_1") (pintype "passive"))
      (node (ref "C_N12+") (pin "1") (pinfunction "1_1") (pintype "passive"))
      (node (ref "C_N21+") (pin "1") (pinfunction "1_1") (pintype "passive"))
      (node (ref "C_N22+") (pin "1") (pinfunction "1_1") (pintype "passive"))
      (node (ref "C_T11+") (pin "1") (pinfunction "1_1") (pintype "passive"))
      (node (ref "C_T12+") (pin "1") (pinfunction "1_1") (pintype "passive"))
      (node (ref "C_T21+") (pin "1") (pinfunction "1_1") (pintype "passive"))
      (node (ref "C_T22+") (pin "1") (pinfunction "1_1") (pintype "passive"))
      (node (ref "H11") (pin "7") (pinfunction "V+_7") (pintype "power_in"))
      (node (ref "H12") (pin "7") (pinfunction "V+_7") (pintype "power_in"))
      (node (ref "H21") (pin "7") (pinfunction "V+_7") (pintype "power_in"))
      (node (ref "H22") (pin "7") (pinfunction "V+_7") (pintype "power_in"))
      (node (ref "JP7") (pin "5") (pinfunction "5_5") (pintype "passive"))
      (node (ref "N11") (pin "7") (pinfunction "V+_7") (pintype "power_in"))
      (node (ref "N12") (pin "7") (pinfunction "V+_7") (pintype "power_in"))
      (node (ref "N21") (pin "7") (pinfunction "V+_7") (pintype "power_in"))
      (node (ref "N22") (pin "7") (pinfunction "V+_7") (pintype "power_in"))
      (node (ref "T11") (pin "7") (pinfunction "V+_7") (pintype "power_in"))
      (node (ref "T12") (pin "7") (pinfunction "V+_7") (pintype "power_in"))
      (node (ref "T21") (pin "7") (pinfunction "V+_7") (pintype "power_in"))
      (node (ref "T22") (pin "7") (pinfunction "V+_7") (pintype "power_in"))
    )
    (net (code "2") (name "+9V") (class "Default")
      (node (ref "C+9") (pin "+") (pinfunction "+_+") (pintype "passive"))
      (node (ref "C_INA1+") (pin "1") (pinfunction "1_1") (pintype "passive"))
      (node (ref "C_INA2+") (pin "1") (pinfunction "1_1") (pintype "passive"))
      (node (ref "INA_1") (pin "7") (pinfunction "+VS_7") (pintype "bidirectional"))
      (node (ref "INA_2") (pin "7") (pinfunction "+VS_7") (pintype "bidirectional"))
      (node (ref "JP7") (pin "3") (pinfunction "3_3") (pintype "passive"))
    )
    (net (code "3") (name "-1.5V") (class "Default")
      (node (ref "C-1.5") (pin "-") (pinfunction "-_-") (pintype "passive"))
      (node (ref "C_H11-") (pin "2") (pinfunction "2_2") (pintype "passive"))
      (node (ref "C_H12-") (pin "2") (pinfunction "2_2") (pintype "passive"))
      (node (ref "C_H21-") (pin "2") (pinfunction "2_2") (pintype "passive"))
      (node (ref "C_H22-") (pin "2") (pinfunction "2_2") (pintype "passive"))
      (node (ref "C_N11-") (pin "2") (pinfunction "2_2") (pintype "passive"))
      (node (ref "C_N12-") (pin "2") (pinfunction "2_2") (pintype "passive"))
      (node (ref "C_N21-") (pin "2") (pinfunction "2_2") (pintype "passive"))
      (node (ref "C_N22-") (pin "2") (pinfunction "2_2") (pintype "passive"))
      (node (ref "C_T11-") (pin "2") (pinfunction "2_2") (pintype "passive"))
      (node (ref "C_T12-") (pin "2") (pinfunction "2_2") (pintype "passive"))
      (node (ref "C_T21-") (pin "2") (pinfunction "2_2") (pintype "passive"))
      (node (ref "C_T22-") (pin "2") (pinfunction "2_2") (pintype "passive"))
      (node (ref "H11") (pin "4") (pinfunction "V-_4") (pintype "power_in"))
      (node (ref "H12") (pin "4") (pinfunction "V-_4") (pintype "power_in"))
      (node (ref "H21") (pin "4") (pinfunction "V-_4") (pintype "power_in"))
      (node (ref "H22") (pin "4") (pinfunction "V-_4") (pintype "power_in"))
      (node (ref "JP7") (pin "4") (pinfunction "4_4") (pintype "passive"))
      (node (ref "N11") (pin "4") (pinfunction "V-_4") (pintype "power_in"))
      (node (ref "N12") (pin "4") (pinfunction "V-_4") (pintype "power_in"))
      (node (ref "N21") (pin "4") (pinfunction "V-_4") (pintype "power_in"))
      (node (ref "N22") (pin "4") (pinfunction "V-_4") (pintype "power_in"))
      (node (ref "T11") (pin "4") (pinfunction "V-_4") (pintype "power_in"))
      (node (ref "T12") (pin "4") (pinfunction "V-_4") (pintype "power_in"))
      (node (ref "T21") (pin "4") (pinfunction "V-_4") (pintype "power_in"))
      (node (ref "T22") (pin "4") (pinfunction "V-_4") (pintype "power_in"))
    )
    (net (code "4") (name "-9V") (class "Default")
      (node (ref "C-9") (pin "-") (pinfunction "-_-") (pintype "passive"))
      (node (ref "C_INA1-") (pin "1") (pinfunction "1_1") (pintype "passive"))
      (node (ref "C_INA2-") (pin "1") (pinfunction "1_1") (pintype "passive"))
      (node (ref "INA_1") (pin "4") (pinfunction "-VS_4") (pintype "bidirectional"))
      (node (ref "INA_2") (pin "4") (pinfunction "-VS_4") (pintype "bidirectional"))
      (node (ref "JP7") (pin "1") (pinfunction "1_1") (pintype "passive"))
    )
    (net (code "5") (name "ACLK") (class "Default")
      (node (ref "CLOCK") (pin "3") (pinfunction "3_3") (pintype "passive"))
      (node (ref "U$1") (pin "35") (pinfunction "P1.2_35") (pintype "bidirectional"))
    )
    (net (code "6") (name "ACT_LED") (class "Default")
      (node (ref "LED7") (pin "C") (pinfunction "C_C") (pintype "passive"))
      (node (ref "U$1") (pin "83") (pinfunction "P6.6_83") (pintype "bidirectional"))
    )
    (net (code "7") (name "AGND") (class "Default")
      (node (ref "C+1.5") (pin "-") (pinfunction "-_-") (pintype "passive"))
      (node (ref "C+9") (pin "-") (pinfunction "-_-") (pintype "passive"))
      (node (ref "C-1.5") (pin "+") (pinfunction "+_+") (pintype "passive"))
      (node (ref "C-9") (pin "+") (pinfunction "+_+") (pintype "passive"))
      (node (ref "C22") (pin "2") (pinfunction "2_2") (pintype "passive"))
      (node (ref "C23") (pin "2") (pinfunction "2_2") (pintype "passive"))
      (node (ref "C28") (pin "2") (pinfunction "2_2") (pintype "passive"))
      (node (ref "C29") (pin "2") (pinfunction "2_2") (pintype "passive"))
      (node (ref "C30") (pin "2") (pinfunction "2_2") (pintype "passive"))
      (node (ref "C31") (pin "2") (pinfunction "2_2") (pintype "passive"))
      (node (ref "C32") (pin "2") (pinfunction "2_2") (pintype "passive"))
      (node (ref "C_H11+") (pin "2") (pinfunction "2_2") (pintype "passive"))
      (node (ref "C_H11-") (pin "1") (pinfunction "1_1") (pintype "passive"))
      (node (ref "C_H12+") (pin "2") (pinfunction "2_2") (pintype "passive"))
      (node (ref "C_H12-") (pin "1") (pinfunction "1_1") (pintype "passive"))
      (node (ref "C_H21+") (pin "2") (pinfunction "2_2") (pintype "passive"))
      (node (ref "C_H21-") (pin "1") (pinfunction "1_1") (pintype "passive"))
      (node (ref "C_H22+") (pin "2") (pinfunction "2_2") (pintype "passive"))
      (node (ref "C_H22-") (pin "1") (pinfunction "1_1") (pintype "passive"))
      (node (ref "C_INA1+") (pin "2") (pinfunction "2_2") (pintype "passive"))
      (node (ref "C_INA1-") (pin "2") (pinfunction "2_2") (pintype "passive"))
      (node (ref "C_INA2+") (pin "2") (pinfunction "2_2") (pintype "passive"))
      (node (ref "C_INA2-") (pin "2") (pinfunction "2_2") (pintype "passive"))
      (node (ref "C_N11+") (pin "2") (pinfunction "2_2") (pintype "passive"))
      (node (ref "C_N11-") (pin "1") (pinfunction "1_1") (pintype "passive"))
      (node (ref "C_N12+") (pin "2") (pinfunction "2_2") (pintype "passive"))
      (node (ref "C_N12-") (pin "1") (pinfunction "1_1") (pintype "passive"))
      (node (ref "C_N21+") (pin "2") (pinfunction "2_2") (pintype "passive"))
      (node (ref "C_N21-") (pin "1") (pinfunction "1_1") (pintype "passive"))
      (node (ref "C_N22+") (pin "2") (pinfunction "2_2") (pintype "passive"))
      (node (ref "C_N22-") (pin "1") (pinfunction "1_1") (pintype "passive"))
      (node (ref "C_T11+") (pin "2") (pinfunction "2_2") (pintype "passive"))
      (node (ref "C_T11-") (pin "1") (pinfunction "1_1") (pintype "passive"))
      (node (ref "C_T11.2") (pin "1") (pinfunction "1_1") (pintype "passive"))
      (node (ref "C_T12+") (pin "2") (pinfunction "2_2") (pintype "passive"))
      (node (ref "C_T12-") (pin "1") (pinfunction "1_1") (pintype "passive"))
      (node (ref "C_T12.2") (pin "1") (pinfunction "1_1") (pintype "passive"))
      (node (ref "C_T21+") (pin "2") (pinfunction "2_2") (pintype "passive"))
      (node (ref "C_T21-") (pin "1") (pinfunction "1_1") (pintype "passive"))
      (node (ref "C_T21.2") (pin "1") (pinfunction "1_1") (pintype "passive"))
      (node (ref "C_T22+") (pin "2") (pinfunction "2_2") (pintype "passive"))
      (node (ref "C_T22-") (pin "1") (pinfunction "1_1") (pintype "passive"))
      (node (ref "C_T22.2") (pin "1") (pinfunction "1_1") (pintype "passive"))
      (node (ref "D2") (pin "1") (pinfunction "A_1") (pintype "passive"))
      (node (ref "D3") (pin "1") (pinfunction "A_1") (pintype "passive"))
      (node (ref "JP7") (pin "2") (pinfunction "2_2") (pintype "passive"))
      (node (ref "JP7") (pin "6") (pinfunction "6_6") (pintype "passive"))
      (node (ref "R2") (pin "2") (pinfunction "2_2") (pintype "passive"))
      (node (ref "R_H11.2") (pin "1") (pinfunction "1_1") (pintype "passive"))
      (node (ref "R_H12.2") (pin "1") (pinfunction "1_1") (pintype "passive"))
      (node (ref "R_H21.2") (pin "1") (pinfunction "1_1") (pintype "passive"))
      (node (ref "R_H22.2") (pin "1") (pinfunction "1_1") (pintype "passive"))
      (node (ref "R_N1.2") (pin "1") (pinfunction "1_1") (pintype "passive"))
      (node (ref "R_N2.2") (pin "1") (pinfunction "1_1") (pintype "passive"))
      (node (ref "U$1") (pin "10") (pinfunction "AVSS2_10") (pintype "bidirectional"))
      (node (ref "U$1") (pin "12") (pinfunction "SD4P0_12") (pintype "bidirectional"))
      (node (ref "U$1") (pin "13") (pinfunction "SD4N0_13") (pintype "bidirectional"))
      (node (ref "U$1") (pin "14") (pinfunction "SD5P0_14") (pintype "bidirectional"))
      (node (ref "U$1") (pin "15") (pinfunction "SD5N0_15") (pintype "bidirectional"))
      (node (ref "U$1") (pin "16") (pinfunction "SD6P0_16") (pintype "bidirectional"))
      (node (ref "U$1") (pin "17") (pinfunction "SD6N0_17") (pintype "bidirectional"))
      (node (ref "U$1") (pin "18") (pinfunction "AVSS1_18") (pintype "bidirectional"))
      (node (ref "U$1") (pin "2") (pinfunction "SD0N0_2") (pintype "bidirectional"))
      (node (ref "U$1") (pin "3") (pinfunction "SD1P0_3") (pintype "bidirectional"))
      (node (ref "U$1") (pin "4") (pinfunction "SD1N0_4") (pintype "bidirectional"))
      (node (ref "U$1") (pin "6") (pinfunction "SD2N0_6") (pintype "bidirectional"))
      (node (ref "U$1") (pin "7") (pinfunction "SD3P0_7") (pintype "bidirectional"))
      (node (ref "U$1") (pin "8") (pinfunction "SD3N0_8") (pintype "bidirectional"))
    )
    (net (code "8") (name "AUXVCC1") (class "Default")
      (node (ref "C26") (pin "1") (pinfunction "1_1") (pintype "passive"))
      (node (ref "C27") (pin "1") (pinfunction "1_1") (pintype "passive"))
      (node (ref "U$1") (pin "22") (pinfunction "AUXVCC1_22") (pintype "bidirectional"))
    )
    (net (code "9") (name "AUXVCC2") (class "Default")
      (node (ref "C24") (pin "1") (pinfunction "1_1") (pintype "passive"))
      (node (ref "C25") (pin "1") (pinfunction "1_1") (pintype "passive"))
      (node (ref "U$1") (pin "21") (pinfunction "AUXVCC2_21") (pintype "bidirectional"))
    )
    (net (code "10") (name "AUXVCC3") (class "Default")
      (node (ref "C43") (pin "1") (pinfunction "1_1") (pintype "passive"))
      (node (ref "C44") (pin "1") (pinfunction "1_1") (pintype "passive"))
      (node (ref "U$1") (pin "29") (pinfunction "AUXVCC3_29") (pintype "bidirectional"))
    )
    (net (code "11") (name "AVCC") (class "Default")
      (node (ref "AVCC") (pin "1") (pinfunction "1_1") (pintype "passive"))
      (node (ref "C29") (pin "1") (pinfunction "1_1") (pintype "passive"))
      (node (ref "C31") (pin "1") (pinfunction "1_1") (pintype "passive"))
      (node (ref "R1") (pin "2") (pinfunction "2_2") (pintype "passive"))
      (node (ref "U$1") (pin "19") (pinfunction "AVCC_19") (pintype "bidirectional"))
    )
    (net (code "12") (name "BTN1") (class "Default")
      (node (ref "R120") (pin "2") (pinfunction "2_2") (pintype "passive"))
      (node (ref "SW1") (pin "1") (pinfunction "1_1") (pintype "passive"))
      (node (ref "U$1") (pin "87") (pinfunction "P7.2_87") (pintype "bidirectional"))
    )
    (net (code "13") (name "BTN2") (class "Default")
      (node (ref "R121") (pin "2") (pinfunction "2_2") (pintype "passive"))
      (node (ref "SW2") (pin "1") (pinfunction "1_1") (pintype "passive"))
      (node (ref "U$1") (pin "86") (pinfunction "P7.1_86") (pintype "bidirectional"))
    )
    (net (code "14") (name "BTN3") (class "Default")
      (node (ref "R122") (pin "2") (pinfunction "2_2") (pintype "passive"))
      (node (ref "SW3") (pin "1") (pinfunction "1_1") (pintype "passive"))
      (node (ref "U$1") (pin "85") (pinfunction "P7.0_85") (pintype "bidirectional"))
    )
    (net (code "15") (name "BTN4") (class "Default")
      (node (ref "R123") (pin "2") (pinfunction "2_2") (pintype "passive"))
      (node (ref "SW4") (pin "1") (pinfunction "1_1") (pintype "passive"))
      (node (ref "U$1") (pin "84") (pinfunction "P6.7_84") (pintype "bidirectional"))
    )
    (net (code "16") (name "DGND") (class "Default")
      (node (ref "C+3") (pin "-") (pinfunction "-_-") (pintype "passive"))
      (node (ref "C100") (pin "2") (pinfunction "2_2") (pintype "passive"))
      (node (ref "C101") (pin "2") (pinfunction "2_2") (pintype "passive"))
      (node (ref "C110") (pin "1") (pinfunction "1_1") (pintype "passive"))
      (node (ref "C24") (pin "2") (pinfunction "2_2") (pintype "passive"))
      (node (ref "C25") (pin "2") (pinfunction "2_2") (pintype "passive"))
      (node (ref "C26") (pin "2") (pinfunction "2_2") (pintype "passive"))
      (node (ref "C27") (pin "2") (pinfunction "2_2") (pintype "passive"))
      (node (ref "C33") (pin "2") (pinfunction "2_2") (pintype "passive"))
      (node (ref "C34") (pin "2") (pinfunction "2_2") (pintype "passive"))
      (node (ref "C35") (pin "2") (pinfunction "2_2") (pintype "passive"))
      (node (ref "C36") (pin "2") (pinfunction "2_2") (pintype "passive"))
      (node (ref "C38") (pin "2") (pinfunction "2_2") (pintype "passive"))
      (node (ref "C43") (pin "2") (pinfunction "2_2") (pintype "passive"))
      (node (ref "C44") (pin "2") (pinfunction "2_2") (pintype "passive"))
      (node (ref "CLOCK") (pin "1") (pinfunction "1_1") (pintype "passive"))
      (node (ref "DGND1") (pin "1") (pinfunction "1_1") (pintype "passive"))
      (node (ref "DGND2") (pin "1") (pinfunction "1_1") (pintype "passive"))
      (node (ref "JP7") (pin "7") (pinfunction "7_7") (pintype "passive"))
      (node (ref "JTAG") (pin "9") (pinfunction "9_9") (pintype "passive"))
      (node (ref "R2") (pin "1") (pinfunction "1_1") (pintype "passive"))
      (node (ref "SW1") (pin "4") (pinfunction "4_4") (pintype "passive"))
      (node (ref "SW2") (pin "4") (pinfunction "4_4") (pintype "passive"))
      (node (ref "SW3") (pin "4") (pinfunction "4_4") (pintype "passive"))
      (node (ref "SW4") (pin "4") (pinfunction "4_4") (pintype "passive"))
      (node (ref "SW5") (pin "4") (pinfunction "4_4") (pintype "passive"))
      (node (ref "U$1") (pin "25") (pinfunction "DVSS1_25") (pintype "bidirectional"))
      (node (ref "U$1") (pin "38") (pinfunction "COM0_38") (pintype "bidirectional"))
      (node (ref "U$1") (pin "39") (pinfunction "COM1_39") (pintype "bidirectional"))
      (node (ref "U$1") (pin "46") (pinfunction "LCDCAP_46") (pintype "bidirectional"))
      (node (ref "U$1") (pin "76") (pinfunction "DVSS2_76") (pintype "bidirectional"))
      (node (ref "XT1") (pin "P3") (pinfunction "3_P3") (pintype "bidirectional"))
    )
    (net (code "17") (name "DVCC") (class "Default")
      (node (ref "C+3") (pin "+") (pinfunction "+_+") (pintype "passive"))
      (node (ref "C33") (pin "1") (pinfunction "1_1") (pintype "passive"))
      (node (ref "C35") (pin "1") (pinfunction "1_1") (pintype "passive"))
      (node (ref "JP14") (pin "2") (pinfunction "2_2") (pintype "passive"))
      (node (ref "JP7") (pin "8") (pinfunction "8_8") (pintype "passive"))
      (node (ref "R1") (pin "1") (pinfunction "1_1") (pintype "passive"))
      (node (ref "R101") (pin "1") (pinfunction "1_1") (pintype "passive"))
      (node (ref "R110") (pin "1") (pinfunction "1_1") (pintype "passive"))
      (node (ref "R111") (pin "1") (pinfunction "1_1") (pintype "passive"))
      (node (ref "R112") (pin "1") (pinfunction "1_1") (pintype "passive"))
      (node (ref "R114") (pin "1") (pinfunction "1_1") (pintype "passive"))
      (node (ref "R115") (pin "1") (pinfunction "1_1") (pintype "passive"))
      (node (ref "R116") (pin "1") (pinfunction "1_1") (pintype "passive"))
      (node (ref "R117") (pin "1") (pinfunction "1_1") (pintype "passive"))
      (node (ref "R120") (pin "1") (pinfunction "1_1") (pintype "passive"))
      (node (ref "R121") (pin "1") (pinfunction "1_1") (pintype "passive"))
      (node (ref "R122") (pin "1") (pinfunction "1_1") (pintype "passive"))
      (node (ref "R123") (pin "1") (pinfunction "1_1") (pintype "passive"))
      (node (ref "U$1") (pin "24") (pinfunction "DVCC_24") (pintype "bidirectional"))
    )
    (net (code "18") (name "DVSYS") (class "Default")
      (node (ref "C34") (pin "1") (pinfunction "1_1") (pintype "passive"))
      (node (ref "C36") (pin "1") (pinfunction "1_1") (pintype "passive"))
      (node (ref "U$1") (pin "23") (pinfunction "VDSYS1_23") (pintype "bidirectional"))
      (node (ref "U$1") (pin "75") (pinfunction "VDSYS2_75") (pintype "bidirectional"))
    )
    (net (code "19") (name "EXT") (class "Default")
      (node (ref "JP14") (pin "3") (pinfunction "3_3") (pintype "passive"))
      (node (ref "JTAG") (pin "4") (pinfunction "4_4") (pintype "passive"))
    )
    (net (code "20") (name "H1_OUT") (class "Default")
      (node (ref "C_H12.0") (pin "1") (pinfunction "1_1") (pintype "passive"))
      (node (ref "H12") (pin "6") (pinfunction "OUT_6") (pintype "output"))
      (node (ref "JP9") (pin "2") (pinfunction "2_2") (pintype "passive"))
      (node (ref "JP9") (pin "4") (pinfunction "4_4") (pintype "passive"))
      (node (ref "JP9") (pin "6") (pinfunction "6_6") (pintype "passive"))
      (node (ref "TP2") (pin "TP") (pinfunction "TP_TP") (pintype "input"))
    )
    (net (code "21") (name "H2_OUT") (class "Default")
      (node (ref "C_H22.0") (pin "1") (pinfunction "1_1") (pintype "passive"))
      (node (ref "H22") (pin "6") (pinfunction "OUT_6") (pintype "output"))
      (node (ref "JP3") (pin "2") (pinfunction "2_2") (pintype "passive"))
      (node (ref "JP3") (pin "4") (pinfunction "4_4") (pintype "passive"))
      (node (ref "JP3") (pin "6") (pinfunction "6_6") (pintype "passive"))
      (node (ref "TP9") (pin "TP") (pinfunction "TP_TP") (pintype "input"))
    )
    (net (code "22") (name "H11_OUT") (class "Default")
      (node (ref "C_H11.0") (pin "1") (pinfunction "1_1") (pintype "passive"))
      (node (ref "C_H12.1") (pin "1") (pinfunction "1_1") (pintype "passive"))
      (node (ref "H11") (pin "6") (pinfunction "OUT_6") (pintype "output"))
      (node (ref "TP15") (pin "TP") (pinfunction "TP_TP") (pintype "input"))
    )
    (net (code "23") (name "H21_OUT") (class "Default")
      (node (ref "C_H21.0") (pin "1") (pinfunction "1_1") (pintype "passive"))
      (node (ref "C_H22.1") (pin "1") (pinfunction "1_1") (pintype "passive"))
      (node (ref "H21") (pin "6") (pinfunction "OUT_6") (pintype "output"))
      (node (ref "TP17") (pin "TP") (pinfunction "TP_TP") (pintype "input"))
    )
    (net (code "24") (name "INA1_OUT") (class "Default")
      (node (ref "INA_1") (pin "6") (pinfunction "OUT_6") (pintype "bidirectional"))
      (node (ref "JP8") (pin "2") (pinfunction "2_2") (pintype "passive"))
      (node (ref "JP8") (pin "4") (pinfunction "4_4") (pintype "passive"))
      (node (ref "JP8") (pin "6") (pinfunction "6_6") (pintype "passive"))
      (node (ref "RZ_1") (pin "2") (pinfunction "2_2") (pintype "passive"))
      (node (ref "TP1") (pin "TP") (pinfunction "TP_TP") (pintype "input"))
    )
    (net (code "25") (name "INA2_OUT") (class "Default")
      (node (ref "INA_2") (pin "6") (pinfunction "OUT_6") (pintype "bidirectional"))
      (node (ref "JP2") (pin "2") (pinfunction "2_2") (pintype "passive"))
      (node (ref "JP2") (pin "4") (pinfunction "4_4") (pintype "passive"))
      (node (ref "JP2") (pin "6") (pinfunction "6_6") (pintype "passive"))
      (node (ref "RZ_2") (pin "2") (pinfunction "2_2") (pintype "passive"))
      (node (ref "TP8") (pin "TP") (pinfunction "TP_TP") (pintype "input"))
    )
    (net (code "26") (name "INT") (class "Default")
      (node (ref "JP14") (pin "1") (pinfunction "1_1") (pintype "passive"))
      (node (ref "JTAG") (pin "2") (pinfunction "2_2") (pintype "passive"))
    )
    (net (code "27") (name "LED1") (class "Default")
      (node (ref "LED1") (pin "C") (pinfunction "C_C") (pintype "passive"))
      (node (ref "U$1") (pin "37") (pinfunction "P1.0_37") (pintype "bidirectional"))
    )
    (net (code "28") (name "LED2") (class "Default")
      (node (ref "LED2") (pin "C") (pinfunction "C_C") (pintype "passive"))
      (node (ref "U$1") (pin "36") (pinfunction "P1.1_36") (pintype "bidirectional"))
    )
    (net (code "29") (name "LED3") (class "Default")
      (node (ref "LED3") (pin "C") (pinfunction "C_C") (pintype "passive"))
      (node (ref "U$1") (pin "34") (pinfunction "P1.3_34") (pintype "bidirectional"))
    )
    (net (code "30") (name "LED4") (class "Default")
      (node (ref "LED4") (pin "C") (pinfunction "C_C") (pintype "passive"))
      (node (ref "U$1") (pin "42") (pinfunction "P2.0_42") (pintype "bidirectional"))
    )
    (net (code "31") (name "LED5") (class "Default")
      (node (ref "LED5") (pin "C") (pinfunction "C_C") (pintype "passive"))
      (node (ref "U$1") (pin "41") (pinfunction "P1.7_41") (pintype "bidirectional"))
    )
    (net (code "32") (name "LED6") (class "Default")
      (node (ref "LED6") (pin "C") (pinfunction "C_C") (pintype "passive"))
      (node (ref "U$1") (pin "40") (pinfunction "P1.6_40") (pintype "bidirectional"))
    )
    (net (code "33") (name "LS+") (class "Default")
      (node (ref "INA_2") (pin "3") (pinfunction "+IN_3") (pintype "bidirectional"))
      (node (ref "R_LS1") (pin "1") (pinfunction "1_1") (pintype "passive"))
      (node (ref "X_LS") (pin "5") (pinfunction "5_5") (pintype "bidirectional"))
    )
    (net (code "34") (name "LS-") (class "Default")
      (node (ref "INA_2") (pin "2") (pinfunction "-IN_2") (pintype "bidirectional"))
      (node (ref "R_LS1") (pin "2") (pinfunction "2_2") (pintype "passive"))
      (node (ref "X_LS") (pin "2") (pinfunction "2_2") (pintype "bidirectional"))
    )
    (net (code "35") (name "LS_TO_ADC2") (class "Default")
      (node (ref "JP16") (pin "2") (pinfunction "2_2") (pintype "passive"))
      (node (ref "JP3") (pin "5") (pinfunction "5_5") (pintype "passive"))
      (node (ref "JP4") (pin "3") (pinfunction "3_3") (pintype "passive"))
      (node (ref "JP6") (pin "1") (pinfunction "1_1") (pintype "passive"))
      (node (ref "TP6") (pin "TP") (pinfunction "TP_TP") (pintype "input"))
    )
    (net (code "36") (name "MCLK") (class "Default")
      (node (ref "CLOCK") (pin "4") (pinfunction "4_4") (pintype "passive"))
      (node (ref "U$1") (pin "33") (pinfunction "P1.4_33") (pintype "bidirectional"))
    )
    (net (code "37") (name "N1_OUT") (class "Default")
      (node (ref "C_N11.0") (pin "1") (pinfunction "1_1") (pintype "passive"))
      (node (ref "JP11") (pin "2") (pinfunction "2_2") (pintype "passive"))
      (node (ref "JP11") (pin "4") (pinfunction "4_4") (pintype "passive"))
      (node (ref "JP11") (pin "6") (pinfunction "6_6") (pintype "passive"))
      (node (ref "N11") (pin "6") (pinfunction "OUT_6") (pintype "output"))
      (node (ref "R_N1.5") (pin "2") (pinfunction "2_2") (pintype "passive"))
      (node (ref "TP4") (pin "TP") (pinfunction "TP_TP") (pintype "input"))
    )
    (net (code "38") (name "N2_OUT") (class "Default")
      (node (ref "C_N21.0") (pin "1") (pinfunction "1_1") (pintype "passive"))
      (node (ref "JP6") (pin "2") (pinfunction "2_2") (pintype "passive"))
      (node (ref "JP6") (pin "4") (pinfunction "4_4") (pintype "passive"))
      (node (ref "JP6") (pin "6") (pinfunction "6_6") (pintype "passive"))
      (node (ref "N21") (pin "6") (pinfunction "OUT_6") (pintype "output"))
      (node (ref "R_N2.5") (pin "2") (pinfunction "2_2") (pintype "passive"))
      (node (ref "TP11") (pin "TP") (pinfunction "TP_TP") (pintype "input"))
    )
    (net (code "39") (name "Net-(C_H11.1-Pad1)") (class "Default")
      (node (ref "C_H11.1") (pin "1") (pinfunction "1_1") (pintype "passive"))
      (node (ref "JP10") (pin "5") (pinfunction "5_5") (pintype "passive"))
      (node (ref "JP11") (pin "5") (pinfunction "5_5") (pintype "passive"))
      (node (ref "JP8") (pin "5") (pinfunction "5_5") (pintype "passive"))
    )
    (net (code "40") (name "Net-(C_H11.1-Pad2)") (class "Default")
      (node (ref "C_H11.1") (pin "2") (pinfunction "2_2") (pintype "passive"))
      (node (ref "C_H11.2") (pin "1") (pinfunction "1_1") (pintype "passive"))
      (node (ref "R_H11.1") (pin "1") (pinfunction "1_1") (pintype "passive"))
    )
    (net (code "41") (name "Net-(C_H12.1-Pad2)") (class "Default")
      (node (ref "C_H12.1") (pin "2") (pinfunction "2_2") (pintype "passive"))
      (node (ref "C_H12.2") (pin "1") (pinfunction "1_1") (pintype "passive"))
      (node (ref "R_H12.1") (pin "1") (pinfunction "1_1") (pintype "passive"))
    )
    (net (code "42") (name "Net-(C_H21.1-Pad1)") (class "Default")
      (node (ref "C_H21.1") (pin "1") (pinfunction "1_1") (pintype "passive"))
      (node (ref "JP2") (pin "5") (pinfunction "5_5") (pintype "passive"))
      (node (ref "JP4") (pin "5") (pinfunction "5_5") (pintype "passive"))
      (node (ref "JP6") (pin "5") (pinfunction "5_5") (pintype "passive"))
    )
    (net (code "43") (name "Net-(C_H21.1-Pad2)") (class "Default")
      (node (ref "C_H21.1") (pin "2") (pinfunction "2_2") (pintype "passive"))
      (node (ref "C_H21.2") (pin "1") (pinfunction "1_1") (pintype "passive"))
      (node (ref "R_H21.1") (pin "1") (pinfunction "1_1") (pintype "passive"))
    )
    (net (code "44") (name "Net-(C_H22.1-Pad2)") (class "Default")
      (node (ref "C_H22.1") (pin "2") (pinfunction "2_2") (pintype "passive"))
      (node (ref "C_H22.2") (pin "1") (pinfunction "1_1") (pintype "passive"))
      (node (ref "R_H22.1") (pin "1") (pinfunction "1_1") (pintype "passive"))
    )
    (net (code "45") (name "Net-(C_N1.1-Pad1)") (class "Default")
      (node (ref "C_N1.1") (pin "1") (pinfunction "1_1") (pintype "passive"))
      (node (ref "JP10") (pin "1") (pinfunction "1_1") (pintype "passive"))
      (node (ref "JP8") (pin "1") (pinfunction "1_1") (pintype "passive"))
      (node (ref "JP9") (pin "1") (pinfunction "1_1") (pintype "passive"))
      (node (ref "R_N1.1") (pin "1") (pinfunction "1_1") (pintype "passive"))
      (node (ref "R_N1.6") (pin "1") (pinfunction "1_1") (pintype "passive"))
    )
    (net (code "46") (name "Net-(C_N2.1-Pad1)") (class "Default")
      (node (ref "C_N2.1") (pin "1") (pinfunction "1_1") (pintype "passive"))
      (node (ref "JP2") (pin "1") (pinfunction "1_1") (pintype "passive"))
      (node (ref "JP3") (pin "1") (pinfunction "1_1") (pintype "passive"))
      (node (ref "JP4") (pin "1") (pinfunction "1_1") (pintype "passive"))
      (node (ref "R_N2.1") (pin "1") (pinfunction "1_1") (pintype "passive"))
      (node (ref "R_N2.6") (pin "1") (pinfunction "1_1") (pintype "passive"))
    )
    (net (code "47") (name "Net-(C_T11.1-Pad1)") (class "Default")
      (node (ref "C_T11.1") (pin "1") (pinfunction "1_1") (pintype "passive"))
      (node (ref "R_T11.1") (pin "2") (pinfunction "2_2") (pintype "passive"))
      (node (ref "R_T11.2") (pin "1") (pinfunction "1_1") (pintype "passive"))
    )
    (net (code "48") (name "Net-(C_T12.1-Pad1)") (class "Default")
      (node (ref "C_T12.1") (pin "1") (pinfunction "1_1") (pintype "passive"))
      (node (ref "R_T12.1") (pin "2") (pinfunction "2_2") (pintype "passive"))
      (node (ref "R_T12.2") (pin "1") (pinfunction "1_1") (pintype "passive"))
    )
    (net (code "49") (name "Net-(C_T21.1-Pad1)") (class "Default")
      (node (ref "C_T21.1") (pin "1") (pinfunction "1_1") (pintype "passive"))
      (node (ref "R_T21.1") (pin "2") (pinfunction "2_2") (pintype "passive"))
      (node (ref "R_T21.2") (pin "1") (pinfunction "1_1") (pintype "passive"))
    )
    (net (code "50") (name "Net-(C_T22.1-Pad1)") (class "Default")
      (node (ref "C_T22.1") (pin "1") (pinfunction "1_1") (pintype "passive"))
      (node (ref "R_T22.1") (pin "2") (pinfunction "2_2") (pintype "passive"))
      (node (ref "R_T22.2") (pin "1") (pinfunction "1_1") (pintype "passive"))
    )
    (net (code "51") (name "Net-(D1-A)") (class "Default")
      (node (ref "D1") (pin "1") (pinfunction "A_1") (pintype "passive"))
      (node (ref "RZ_1") (pin "1") (pinfunction "1_1") (pintype "passive"))
    )
    (net (code "52") (name "Net-(D1-C)") (class "Default")
      (node (ref "D1") (pin "3") (pinfunction "C_3") (pintype "passive"))
      (node (ref "D2") (pin "3") (pinfunction "C_3") (pintype "passive"))
    )
    (net (code "53") (name "Net-(D3-C)") (class "Default")
      (node (ref "D3") (pin "3") (pinfunction "C_3") (pintype "passive"))
      (node (ref "D4") (pin "3") (pinfunction "C_3") (pintype "passive"))
    )
    (net (code "54") (name "Net-(D4-A)") (class "Default")
      (node (ref "D4") (pin "1") (pinfunction "A_1") (pintype "passive"))
      (node (ref "RZ_2") (pin "1") (pinfunction "1_1") (pintype "passive"))
    )
    (net (code "55") (name "Net-(H11-IN+)") (class "Default")
      (node (ref "C_H11.2") (pin "2") (pinfunction "2_2") (pintype "passive"))
      (node (ref "H11") (pin "3") (pinfunction "IN+_3") (pintype "input"))
      (node (ref "R_H11.2") (pin "2") (pinfunction "2_2") (pintype "passive"))
    )
    (net (code "56") (name "Net-(H11-IN-)") (class "Default")
      (node (ref "C_H11.0") (pin "2") (pinfunction "2_2") (pintype "passive"))
      (node (ref "H11") (pin "2") (pinfunction "IN-_2") (pintype "input"))
      (node (ref "R_H11.1") (pin "2") (pinfunction "2_2") (pintype "passive"))
    )
    (net (code "57") (name "Net-(H12-IN+)") (class "Default")
      (node (ref "C_H12.2") (pin "2") (pinfunction "2_2") (pintype "passive"))
      (node (ref "H12") (pin "3") (pinfunction "IN+_3") (pintype "input"))
      (node (ref "R_H12.2") (pin "2") (pinfunction "2_2") (pintype "passive"))
    )
    (net (code "58") (name "Net-(H12-IN-)") (class "Default")
      (node (ref "C_H12.0") (pin "2") (pinfunction "2_2") (pintype "passive"))
      (node (ref "H12") (pin "2") (pinfunction "IN-_2") (pintype "input"))
      (node (ref "R_H12.1") (pin "2") (pinfunction "2_2") (pintype "passive"))
    )
    (net (code "59") (name "Net-(H21-IN+)") (class "Default")
      (node (ref "C_H21.2") (pin "2") (pinfunction "2_2") (pintype "passive"))
      (node (ref "H21") (pin "3") (pinfunction "IN+_3") (pintype "input"))
      (node (ref "R_H21.2") (pin "2") (pinfunction "2_2") (pintype "passive"))
    )
    (net (code "60") (name "Net-(H21-IN-)") (class "Default")
      (node (ref "C_H21.0") (pin "2") (pinfunction "2_2") (pintype "passive"))
      (node (ref "H21") (pin "2") (pinfunction "IN-_2") (pintype "input"))
      (node (ref "R_H21.1") (pin "2") (pinfunction "2_2") (pintype "passive"))
    )
    (net (code "61") (name "Net-(H22-IN+)") (class "Default")
      (node (ref "C_H22.2") (pin "2") (pinfunction "2_2") (pintype "passive"))
      (node (ref "H22") (pin "3") (pinfunction "IN+_3") (pintype "input"))
      (node (ref "R_H22.2") (pin "2") (pinfunction "2_2") (pintype "passive"))
    )
    (net (code "62") (name "Net-(H22-IN-)") (class "Default")
      (node (ref "C_H22.0") (pin "2") (pinfunction "2_2") (pintype "passive"))
      (node (ref "H22") (pin "2") (pinfunction "IN-_2") (pintype "input"))
      (node (ref "R_H22.1") (pin "2") (pinfunction "2_2") (pintype "passive"))
    )
    (net (code "63") (name "Net-(INA_1-RG-Pad1)") (class "Default")
      (node (ref "INA_1") (pin "1") (pinfunction "RG_1") (pintype "bidirectional"))
      (node (ref "JP5") (pin "1") (pinfunction "1_1") (pintype "passive"))
      (node (ref "JP5") (pin "3") (pinfunction "3_3") (pintype "passive"))
    )
    (net (code "64") (name "Net-(INA_1-RG-Pad8)") (class "Default")
      (node (ref "INA_1") (pin "8") (pinfunction "RG_8") (pintype "bidirectional"))
      (node (ref "R_INA1_CONST") (pin "2") (pinfunction "2_2") (pintype "passive"))
      (node (ref "R_INA1_MIN") (pin "2") (pinfunction "2_2") (pintype "passive"))
    )
    (net (code "65") (name "Net-(INA_2-RG-Pad1)") (class "Default")
      (node (ref "INA_2") (pin "1") (pinfunction "RG_1") (pintype "bidirectional"))
      (node (ref "JP1") (pin "1") (pinfunction "1_1") (pintype "passive"))
      (node (ref "JP1") (pin "3") (pinfunction "3_3") (pintype "passive"))
    )
    (net (code "66") (name "Net-(INA_2-RG-Pad8)") (class "Default")
      (node (ref "INA_2") (pin "8") (pinfunction "RG_8") (pintype "bidirectional"))
      (node (ref "R_INA2_CONST") (pin "2") (pinfunction "2_2") (pintype "passive"))
      (node (ref "R_INA2_MIN") (pin "2") (pinfunction "2_2") (pintype "passive"))
    )
    (net (code "67") (name "Net-(JP1-Pad4)") (class "Default")
      (node (ref "JP1") (pin "4") (pinfunction "4_4") (pintype "passive"))
      (node (ref "R_INA2_CONST") (pin "1") (pinfunction "1_1") (pintype "passive"))
    )
    (net (code "68") (name "Net-(JP2-Pad3)") (class "Default")
      (node (ref "JP2") (pin "3") (pinfunction "3_3") (pintype "passive"))
      (node (ref "JP3") (pin "3") (pinfunction "3_3") (pintype "passive"))
      (node (ref "JP6") (pin "3") (pinfunction "3_3") (pintype "passive"))
      (node (ref "R_T21.1") (pin "1") (pinfunction "1_1") (pintype "passive"))
    )
    (net (code "69") (name "Net-(JP5-Pad4)") (class "Default")
      (node (ref "JP5") (pin "4") (pinfunction "4_4") (pintype "passive"))
      (node (ref "R_INA1_CONST") (pin "1") (pinfunction "1_1") (pintype "passive"))
    )
    (net (code "70") (name "Net-(JP11-Pad3)") (class "Default")
      (node (ref "JP11") (pin "3") (pinfunction "3_3") (pintype "passive"))
      (node (ref "JP8") (pin "3") (pinfunction "3_3") (pintype "passive"))
      (node (ref "JP9") (pin "3") (pinfunction "3_3") (pintype "passive"))
      (node (ref "R_T11.1") (pin "1") (pinfunction "1_1") (pintype "passive"))
    )
    (net (code "71") (name "Net-(JP12-Pad2)") (class "Default")
      (node (ref "JP12") (pin "2") (pinfunction "2_2") (pintype "passive"))
      (node (ref "X_LS") (pin "1") (pinfunction "1_1") (pintype "bidirectional"))
    )
    (net (code "72") (name "Net-(JP13-Pad2)") (class "Default")
      (node (ref "JP13") (pin "2") (pinfunction "2_2") (pintype "passive"))
      (node (ref "X_RS") (pin "1") (pinfunction "1_1") (pintype "bidirectional"))
    )
    (net (code "73") (name "Net-(LED1-PadA)") (class "Default")
      (node (ref "LED1") (pin "A") (pinfunction "A_A") (pintype "passive"))
      (node (ref "R114") (pin "2") (pinfunction "2_2") (pintype "passive"))
    )
    (net (code "74") (name "Net-(LED2-PadA)") (class "Default")
      (node (ref "LED2") (pin "A") (pinfunction "A_A") (pintype "passive"))
      (node (ref "R115") (pin "2") (pinfunction "2_2") (pintype "passive"))
    )
    (net (code "75") (name "Net-(LED3-PadA)") (class "Default")
      (node (ref "LED3") (pin "A") (pinfunction "A_A") (pintype "passive"))
      (node (ref "R116") (pin "2") (pinfunction "2_2") (pintype "passive"))
    )
    (net (code "76") (name "Net-(LED4-PadA)") (class "Default")
      (node (ref "LED4") (pin "A") (pinfunction "A_A") (pintype "passive"))
      (node (ref "R110") (pin "2") (pinfunction "2_2") (pintype "passive"))
    )
    (net (code "77") (name "Net-(LED5-PadA)") (class "Default")
      (node (ref "LED5") (pin "A") (pinfunction "A_A") (pintype "passive"))
      (node (ref "R111") (pin "2") (pinfunction "2_2") (pintype "passive"))
    )
    (net (code "78") (name "Net-(LED6-PadA)") (class "Default")
      (node (ref "LED6") (pin "A") (pinfunction "A_A") (pintype "passive"))
      (node (ref "R112") (pin "2") (pinfunction "2_2") (pintype "passive"))
    )
    (net (code "79") (name "Net-(LED7-PadA)") (class "Default")
      (node (ref "LED7") (pin "A") (pinfunction "A_A") (pintype "passive"))
      (node (ref "R117") (pin "2") (pinfunction "2_2") (pintype "passive"))
    )
    (net (code "80") (name "Net-(N11-IN+)") (class "Default")
      (node (ref "C_N1.1") (pin "2") (pinfunction "2_2") (pintype "passive"))
      (node (ref "N11") (pin "3") (pinfunction "IN+_3") (pintype "input"))
      (node (ref "R_N1.1") (pin "2") (pinfunction "2_2") (pintype "passive"))
      (node (ref "R_N1.2") (pin "2") (pinfunction "2_2") (pintype "passive"))
      (node (ref "R_N1.3") (pin "2") (pinfunction "2_2") (pintype "passive"))
      (node (ref "R_N1.3PARALLEL") (pin "2") (pinfunction "2_2") (pintype "passive"))
    )
    (net (code "81") (name "Net-(N11-IN-)") (class "Default")
      (node (ref "C_N1.2") (pin "2") (pinfunction "2_2") (pintype "passive"))
      (node (ref "C_N11.0") (pin "2") (pinfunction "2_2") (pintype "passive"))
      (node (ref "N11") (pin "2") (pinfunction "IN-_2") (pintype "input"))
      (node (ref "R_N1.4") (pin "1") (pinfunction "1_1") (pintype "passive"))
      (node (ref "R_N1.4PARALLEL") (pin "1") (pinfunction "1_1") (pintype "passive"))
    )
    (net (code "82") (name "Net-(N12-IN+)") (class "Default")
      (node (ref "N12") (pin "3") (pinfunction "IN+_3") (pintype "input"))
      (node (ref "R_N1.5") (pin "1") (pinfunction "1_1") (pintype "passive"))
      (node (ref "R_N1.6") (pin "2") (pinfunction "2_2") (pintype "passive"))
    )
    (net (code "83") (name "Net-(N12-IN-)") (class "Default")
      (node (ref "C_N12.0") (pin "1") (pinfunction "1_1") (pintype "passive"))
      (node (ref "N12") (pin "2") (pinfunction "IN-_2") (pintype "input"))
      (node (ref "R_N1.4PARALLEL") (pin "2") (pinfunction "2_2") (pintype "passive"))
      (node (ref "R_N1.4SERIELL") (pin "2") (pinfunction "2_2") (pintype "passive"))
    )
    (net (code "84") (name "Net-(N12-OUT)") (class "Default")
      (node (ref "C_N1.2") (pin "1") (pinfunction "1_1") (pintype "passive"))
      (node (ref "C_N12.0") (pin "2") (pinfunction "2_2") (pintype "passive"))
      (node (ref "N12") (pin "6") (pinfunction "OUT_6") (pintype "output"))
      (node (ref "R_N1.3PARALLEL") (pin "1") (pinfunction "1_1") (pintype "passive"))
      (node (ref "R_N1.3SERIELL") (pin "1") (pinfunction "1_1") (pintype "passive"))
    )
    (net (code "85") (name "Net-(N21-IN+)") (class "Default")
      (node (ref "C_N2.1") (pin "2") (pinfunction "2_2") (pintype "passive"))
      (node (ref "N21") (pin "3") (pinfunction "IN+_3") (pintype "input"))
      (node (ref "R_N2.1") (pin "2") (pinfunction "2_2") (pintype "passive"))
      (node (ref "R_N2.2") (pin "2") (pinfunction "2_2") (pintype "passive"))
      (node (ref "R_N2.3") (pin "2") (pinfunction "2_2") (pintype "passive"))
      (node (ref "R_N2.3PARALLEL") (pin "2") (pinfunction "2_2") (pintype "passive"))
    )
    (net (code "86") (name "Net-(N21-IN-)") (class "Default")
      (node (ref "C_N2.2") (pin "2") (pinfunction "2_2") (pintype "passive"))
      (node (ref "C_N21.0") (pin "2") (pinfunction "2_2") (pintype "passive"))
      (node (ref "N21") (pin "2") (pinfunction "IN-_2") (pintype "input"))
      (node (ref "R_N2.4") (pin "1") (pinfunction "1_1") (pintype "passive"))
      (node (ref "R_N2.4PARALLEL") (pin "1") (pinfunction "1_1") (pintype "passive"))
    )
    (net (code "87") (name "Net-(N22-IN+)") (class "Default")
      (node (ref "N22") (pin "3") (pinfunction "IN+_3") (pintype "input"))
      (node (ref "R_N2.5") (pin "1") (pinfunction "1_1") (pintype "passive"))
      (node (ref "R_N2.6") (pin "2") (pinfunction "2_2") (pintype "passive"))
    )
    (net (code "88") (name "Net-(N22-IN-)") (class "Default")
      (node (ref "C_N22.0") (pin "1") (pinfunction "1_1") (pintype "passive"))
      (node (ref "N22") (pin "2") (pinfunction "IN-_2") (pintype "input"))
      (node (ref "R_N2.4PARALLEL") (pin "2") (pinfunction "2_2") (pintype "passive"))
      (node (ref "R_N2.4SERIAL") (pin "2") (pinfunction "2_2") (pintype "passive"))
    )
    (net (code "89") (name "Net-(N22-OUT)") (class "Default")
      (node (ref "C_N2.2") (pin "1") (pinfunction "1_1") (pintype "passive"))
      (node (ref "C_N22.0") (pin "2") (pinfunction "2_2") (pintype "passive"))
      (node (ref "N22") (pin "6") (pinfunction "OUT_6") (pintype "output"))
      (node (ref "R_N2.3PARALLEL") (pin "1") (pinfunction "1_1") (pintype "passive"))
      (node (ref "R_N2.3SERIELL") (pin "1") (pinfunction "1_1") (pintype "passive"))
    )
    (net (code "90") (name "Net-(R_INA1_VAR-A)") (class "Default")
      (node (ref "JP5") (pin "2") (pinfunction "2_2") (pintype "passive"))
      (node (ref "R_INA1_VAR") (pin "1") (pinfunction "A_1") (pintype "passive"))
    )
    (net (code "91") (name "Net-(R_INA1_VAR-S)") (class "Default")
      (node (ref "R_INA1_MIN") (pin "1") (pinfunction "1_1") (pintype "passive"))
      (node (ref "R_INA1_VAR") (pin "2") (pinfunction "S_2") (pintype "passive"))
    )
    (net (code "92") (name "Net-(R_INA2_VAR-A)") (class "Default")
      (node (ref "JP1") (pin "2") (pinfunction "2_2") (pintype "passive"))
      (node (ref "R_INA2_VAR") (pin "1") (pinfunction "A_1") (pintype "passive"))
    )
    (net (code "93") (name "Net-(R_INA2_VAR-S)") (class "Default")
      (node (ref "R_INA2_MIN") (pin "1") (pinfunction "1_1") (pintype "passive"))
      (node (ref "R_INA2_VAR") (pin "2") (pinfunction "S_2") (pintype "passive"))
    )
    (net (code "94") (name "Net-(R_N1.3-Pad1)") (class "Default")
      (node (ref "R_N1.3") (pin "1") (pinfunction "1_1") (pintype "passive"))
      (node (ref "R_N1.3SERIELL") (pin "2") (pinfunction "2_2") (pintype "passive"))
    )
    (net (code "95") (name "Net-(R_N1.4-Pad2)") (class "Default")
      (node (ref "R_N1.4") (pin "2") (pinfunction "2_2") (pintype "passive"))
      (node (ref "R_N1.4SERIELL") (pin "1") (pinfunction "1_1") (pintype "passive"))
    )
    (net (code "96") (name "Net-(R_N2.3-Pad1)") (class "Default")
      (node (ref "R_N2.3") (pin "1") (pinfunction "1_1") (pintype "passive"))
      (node (ref "R_N2.3SERIELL") (pin "2") (pinfunction "2_2") (pintype "passive"))
    )
    (net (code "97") (name "Net-(R_N2.4-Pad2)") (class "Default")
      (node (ref "R_N2.4") (pin "2") (pinfunction "2_2") (pintype "passive"))
      (node (ref "R_N2.4SERIAL") (pin "1") (pinfunction "1_1") (pintype "passive"))
    )
    (net (code "98") (name "Net-(T11-IN+)") (class "Default")
      (node (ref "C_T11.2") (pin "2") (pinfunction "2_2") (pintype "passive"))
      (node (ref "R_T11.2") (pin "2") (pinfunction "2_2") (pintype "passive"))
      (node (ref "T11") (pin "3") (pinfunction "IN+_3") (pintype "input"))
    )
    (net (code "99") (name "Net-(T11-IN-)") (class "Default")
      (node (ref "C_T11.0") (pin "2") (pinfunction "2_2") (pintype "passive"))
      (node (ref "C_T11.1") (pin "2") (pinfunction "2_2") (pintype "passive"))
      (node (ref "T11") (pin "2") (pinfunction "IN-_2") (pintype "input"))
    )
    (net (code "100") (name "Net-(T12-IN+)") (class "Default")
      (node (ref "C_T12.2") (pin "2") (pinfunction "2_2") (pintype "passive"))
      (node (ref "R_T12.2") (pin "2") (pinfunction "2_2") (pintype "passive"))
      (node (ref "T12") (pin "3") (pinfunction "IN+_3") (pintype "input"))
    )
    (net (code "101") (name "Net-(T12-IN-)") (class "Default")
      (node (ref "C_T12.0") (pin "2") (pinfunction "2_2") (pintype "passive"))
      (node (ref "C_T12.1") (pin "2") (pinfunction "2_2") (pintype "passive"))
      (node (ref "T12") (pin "2") (pinfunction "IN-_2") (pintype "input"))
    )
    (net (code "102") (name "Net-(T21-IN+)") (class "Default")
      (node (ref "C_T21.2") (pin "2") (pinfunction "2_2") (pintype "passive"))
      (node (ref "R_T21.2") (pin "2") (pinfunction "2_2") (pintype "passive"))
      (node (ref "T21") (pin "3") (pinfunction "IN+_3") (pintype "input"))
    )
    (net (code "103") (name "Net-(T21-IN-)") (class "Default")
      (node (ref "C_T21.0") (pin "2") (pinfunction "2_2") (pintype "passive"))
      (node (ref "C_T21.1") (pin "2") (pinfunction "2_2") (pintype "passive"))
      (node (ref "T21") (pin "2") (pinfunction "IN-_2") (pintype "input"))
    )
    (net (code "104") (name "Net-(T22-IN+)") (class "Default")
      (node (ref "C_T22.2") (pin "2") (pinfunction "2_2") (pintype "passive"))
      (node (ref "R_T22.2") (pin "2") (pinfunction "2_2") (pintype "passive"))
      (node (ref "T22") (pin "3") (pinfunction "IN+_3") (pintype "input"))
    )
    (net (code "105") (name "Net-(T22-IN-)") (class "Default")
      (node (ref "C_T22.0") (pin "2") (pinfunction "2_2") (pintype "passive"))
      (node (ref "C_T22.1") (pin "2") (pinfunction "2_2") (pintype "passive"))
      (node (ref "T22") (pin "2") (pinfunction "IN-_2") (pintype "input"))
    )
    (net (code "106") (name "Net-(U$1-P3.0)") (class "Default")
      (node (ref "P1") (pin "1") (pinfunction "1_1") (pintype "passive"))
      (node (ref "U$1") (pin "51") (pinfunction "P3.0_51") (pintype "bidirectional"))
    )
    (net (code "107") (name "Net-(U$1-P3.1)") (class "Default")
      (node (ref "P1") (pin "2") (pinfunction "2_2") (pintype "passive"))
      (node (ref "U$1") (pin "52") (pinfunction "P3.1_52") (pintype "bidirectional"))
    )
    (net (code "108") (name "Net-(U$1-P3.2)") (class "Default")
      (node (ref "P1") (pin "3") (pinfunction "3_3") (pintype "passive"))
      (node (ref "U$1") (pin "53") (pinfunction "P3.2_53") (pintype "bidirectional"))
    )
    (net (code "109") (name "Net-(U$1-P3.3)") (class "Default")
      (node (ref "P1") (pin "4") (pinfunction "4_4") (pintype "passive"))
      (node (ref "U$1") (pin "54") (pinfunction "P3.3_54") (pintype "bidirectional"))
    )
    (net (code "110") (name "Net-(U$1-P3.4)") (class "Default")
      (node (ref "P1") (pin "5") (pinfunction "5_5") (pintype "passive"))
      (node (ref "U$1") (pin "55") (pinfunction "P3.4_55") (pintype "bidirectional"))
    )
    (net (code "111") (name "Net-(U$1-P3.5)") (class "Default")
      (node (ref "P1") (pin "6") (pinfunction "6_6") (pintype "passive"))
      (node (ref "U$1") (pin "56") (pinfunction "P3.5_56") (pintype "bidirectional"))
    )
    (net (code "112") (name "Net-(U$1-P3.6)") (class "Default")
      (node (ref "P1") (pin "7") (pinfunction "7_7") (pintype "passive"))
      (node (ref "U$1") (pin "57") (pinfunction "P3.6_57") (pintype "bidirectional"))
    )
    (net (code "113") (name "Net-(U$1-P3.7)") (class "Default")
      (node (ref "P1") (pin "8") (pinfunction "8_8") (pintype "passive"))
      (node (ref "U$1") (pin "58") (pinfunction "P3.7_58") (pintype "bidirectional"))
    )
    (net (code "114") (name "Net-(U$1-P4.0)") (class "Default")
      (node (ref "P4") (pin "1") (pinfunction "1_1") (pintype "passive"))
      (node (ref "U$1") (pin "59") (pinfunction "P4.0_59") (pintype "bidirectional"))
    )
    (net (code "115") (name "Net-(U$1-P4.3)") (class "Default")
      (node (ref "P4") (pin "4") (pinfunction "4_4") (pintype "passive"))
      (node (ref "U$1") (pin "62") (pinfunction "P4.3_62") (pintype "bidirectional"))
    )
    (net (code "116") (name "Net-(U$1-P4.4)") (class "Default")
      (node (ref "P4") (pin "5") (pinfunction "5_5") (pintype "passive"))
      (node (ref "U$1") (pin "63") (pinfunction "P4.4_63") (pintype "bidirectional"))
    )
    (net (code "117") (name "Net-(U$1-P4.5)") (class "Default")
      (node (ref "P4") (pin "6") (pinfunction "6_6") (pintype "passive"))
      (node (ref "U$1") (pin "64") (pinfunction "P4.5_64") (pintype "bidirectional"))
    )
    (net (code "118") (name "Net-(U$1-P4.6)") (class "Default")
      (node (ref "P4") (pin "7") (pinfunction "7_7") (pintype "passive"))
      (node (ref "U$1") (pin "65") (pinfunction "P4.6_65") (pintype "bidirectional"))
    )
    (net (code "119") (name "Net-(U$1-P4.7)") (class "Default")
      (node (ref "P4") (pin "8") (pinfunction "8_8") (pintype "passive"))
      (node (ref "U$1") (pin "66") (pinfunction "P4.7_66") (pintype "bidirectional"))
    )
    (net (code "120") (name "Net-(U$1-P5.0)") (class "Default")
      (node (ref "P5") (pin "1") (pinfunction "1_1") (pintype "passive"))
      (node (ref "U$1") (pin "67") (pinfunction "P5.0_67") (pintype "bidirectional"))
    )
    (net (code "121") (name "Net-(U$1-P5.1)") (class "Default")
      (node (ref "P5") (pin "2") (pinfunction "2_2") (pintype "passive"))
      (node (ref "U$1") (pin "68") (pinfunction "P5.1_68") (pintype "bidirectional"))
    )
    (net (code "122") (name "Net-(U$1-P5.2)") (class "Default")
      (node (ref "P5") (pin "3") (pinfunction "3_3") (pintype "passive"))
      (node (ref "U$1") (pin "69") (pinfunction "P5.2_69") (pintype "bidirectional"))
    )
    (net (code "123") (name "Net-(U$1-P5.3)") (class "Default")
      (node (ref "P5") (pin "4") (pinfunction "4_4") (pintype "passive"))
      (node (ref "U$1") (pin "70") (pinfunction "P5.3_70") (pintype "bidirectional"))
    )
    (net (code "124") (name "Net-(U$1-P5.4)") (class "Default")
      (node (ref "P5") (pin "5") (pinfunction "5_5") (pintype "passive"))
      (node (ref "U$1") (pin "71") (pinfunction "P5.4_71") (pintype "bidirectional"))
    )
    (net (code "125") (name "Net-(U$1-P5.5)") (class "Default")
      (node (ref "P5") (pin "6") (pinfunction "6_6") (pintype "passive"))
      (node (ref "U$1") (pin "72") (pinfunction "P5.5_72") (pintype "bidirectional"))
    )
    (net (code "126") (name "Net-(U$1-P5.6)") (class "Default")
      (node (ref "P5") (pin "7") (pinfunction "7_7") (pintype "passive"))
      (node (ref "U$1") (pin "73") (pinfunction "P5.6_73") (pintype "bidirectional"))
    )
    (net (code "127") (name "Net-(U$1-P5.7)") (class "Default")
      (node (ref "P5") (pin "8") (pinfunction "8_8") (pintype "passive"))
      (node (ref "U$1") (pin "74") (pinfunction "P5.7_74") (pintype "bidirectional"))
    )
    (net (code "128") (name "Net-(U$1-P6.0)") (class "Default")
      (node (ref "P6") (pin "1") (pinfunction "1_1") (pintype "passive"))
      (node (ref "U$1") (pin "77") (pinfunction "P6.0_77") (pintype "bidirectional"))
    )
    (net (code "129") (name "Net-(U$1-P6.1)") (class "Default")
      (node (ref "P6") (pin "2") (pinfunction "2_2") (pintype "passive"))
      (node (ref "U$1") (pin "78") (pinfunction "P6.1_78") (pintype "bidirectional"))
    )
    (net (code "130") (name "Net-(U$1-P6.2)") (class "Default")
      (node (ref "P6") (pin "3") (pinfunction "3_3") (pintype "passive"))
      (node (ref "U$1") (pin "79") (pinfunction "P6.2_79") (pintype "bidirectional"))
    )
    (net (code "131") (name "Net-(U$1-P6.3)") (class "Default")
      (node (ref "P6") (pin "4") (pinfunction "4_4") (pintype "passive"))
      (node (ref "U$1") (pin "80") (pinfunction "P6.3_80") (pintype "bidirectional"))
    )
    (net (code "132") (name "Net-(U$1-P6.4)") (class "Default")
      (node (ref "P6") (pin "5") (pinfunction "5_5") (pintype "passive"))
      (node (ref "U$1") (pin "81") (pinfunction "P6.4_81") (pintype "bidirectional"))
    )
    (net (code "133") (name "Net-(U$1-P6.5)") (class "Default")
      (node (ref "P6") (pin "6") (pinfunction "6_6") (pintype "passive"))
      (node (ref "U$1") (pin "82") (pinfunction "P6.5_82") (pintype "bidirectional"))
    )
    (net (code "134") (name "REF") (class "Default")
      (node (ref "INA_1") (pin "5") (pinfunction "REF_5") (pintype "bidirectional"))
      (node (ref "INA_2") (pin "5") (pinfunction "REF_5") (pintype "bidirectional"))
      (node (ref "JP12") (pin "1") (pinfunction "1_1") (pintype "passive"))
      (node (ref "JP13") (pin "1") (pinfunction "1_1") (pintype "passive"))
    )
    (net (code "135") (name "RESET") (class "Default")
      (node (ref "C110") (pin "2") (pinfunction "2_2") (pintype "passive"))
      (node (ref "JTAG") (pin "11") (pinfunction "11_11") (pintype "passive"))
      (node (ref "R101") (pin "2") (pinfunction "2_2") (pintype "passive"))
      (node (ref "SW5") (pin "1") (pinfunction "1_1") (pintype "passive"))
      (node (ref "U$1") (pin "100") (pinfunction "RST/NMI/SBTDIO_100") (pintype "bidirectional"))
    )
    (net (code "136") (name "RS+") (class "Default")
      (node (ref "INA_1") (pin "3") (pinfunction "+IN_3") (pintype "bidirectional"))
      (node (ref "R_RS") (pin "1") (pinfunction "1_1") (pintype "passive"))
      (node (ref "X_RS") (pin "5") (pinfunction "5_5") (pintype "bidirectional"))
    )
    (net (code "137") (name "RS-") (class "Default")
      (node (ref "INA_1") (pin "2") (pinfunction "-IN_2") (pintype "bidirectional"))
      (node (ref "R_RS") (pin "2") (pinfunction "2_2") (pintype "passive"))
      (node (ref "X_RS") (pin "2") (pinfunction "2_2") (pintype "bidirectional"))
    )
    (net (code "138") (name "RS_TO_ADC1") (class "Default")
      (node (ref "JP10") (pin "3") (pinfunction "3_3") (pintype "passive"))
      (node (ref "JP11") (pin "1") (pinfunction "1_1") (pintype "passive"))
      (node (ref "JP15") (pin "2") (pinfunction "2_2") (pintype "passive"))
      (node (ref "JP9") (pin "5") (pinfunction "5_5") (pintype "passive"))
      (node (ref "TP5") (pin "TP") (pinfunction "TP_TP") (pintype "input"))
    )
    (net (code "139") (name "RTCCLK") (class "Default")
      (node (ref "CLOCK") (pin "2") (pinfunction "2_2") (pintype "passive"))
      (node (ref "U$1") (pin "94") (pinfunction "P8.1_94") (pintype "bidirectional"))
    )
    (net (code "140") (name "SD_IN_1P") (class "Default")
      (node (ref "JP15") (pin "1") (pinfunction "1_1") (pintype "passive"))
      (node (ref "U$1") (pin "1") (pinfunction "SD0P0_1") (pintype "bidirectional"))
    )
    (net (code "141") (name "SD_IN_2P") (class "Default")
      (node (ref "JP16") (pin "1") (pinfunction "1_1") (pintype "passive"))
      (node (ref "U$1") (pin "5") (pinfunction "SD2P0_5") (pintype "bidirectional"))
    )
    (net (code "142") (name "SMCLK") (class "Default")
      (node (ref "CLOCK") (pin "5") (pinfunction "5_5") (pintype "passive"))
      (node (ref "U$1") (pin "32") (pinfunction "P1.5_32") (pintype "bidirectional"))
    )
    (net (code "143") (name "T1_OUT") (class "Default")
      (node (ref "C_T12.0") (pin "1") (pinfunction "1_1") (pintype "passive"))
      (node (ref "JP10") (pin "2") (pinfunction "2_2") (pintype "passive"))
      (node (ref "JP10") (pin "4") (pinfunction "4_4") (pintype "passive"))
      (node (ref "JP10") (pin "6") (pinfunction "6_6") (pintype "passive"))
      (node (ref "T12") (pin "6") (pinfunction "OUT_6") (pintype "output"))
      (node (ref "TP3") (pin "TP") (pinfunction "TP_TP") (pintype "input"))
    )
    (net (code "144") (name "T2_OUT") (class "Default")
      (node (ref "C_T22.0") (pin "1") (pinfunction "1_1") (pintype "passive"))
      (node (ref "JP4") (pin "2") (pinfunction "2_2") (pintype "passive"))
      (node (ref "JP4") (pin "4") (pinfunction "4_4") (pintype "passive"))
      (node (ref "JP4") (pin "6") (pinfunction "6_6") (pintype "passive"))
      (node (ref "T22") (pin "6") (pinfunction "OUT_6") (pintype "output"))
      (node (ref "TP10") (pin "TP") (pinfunction "TP_TP") (pintype "input"))
    )
    (net (code "145") (name "T11_OUT") (class "Default")
      (node (ref "C_T11.0") (pin "1") (pinfunction "1_1") (pintype "passive"))
      (node (ref "R_T12.1") (pin "1") (pinfunction "1_1") (pintype "passive"))
      (node (ref "T11") (pin "6") (pinfunction "OUT_6") (pintype "output"))
      (node (ref "TP16") (pin "TP") (pinfunction "TP_TP") (pintype "input"))
    )
    (net (code "146") (name "T21_OUT") (class "Default")
      (node (ref "C_T21.0") (pin "1") (pinfunction "1_1") (pintype "passive"))
      (node (ref "R_T22.1") (pin "1") (pinfunction "1_1") (pintype "passive"))
      (node (ref "T21") (pin "6") (pinfunction "OUT_6") (pintype "output"))
      (node (ref "TP18") (pin "TP") (pinfunction "TP_TP") (pintype "input"))
    )
    (net (code "147") (name "TCK") (class "Default")
      (node (ref "JTAG") (pin "7") (pinfunction "7_7") (pintype "passive"))
      (node (ref "U$1") (pin "99") (pinfunction "PJ.3/TCK_99") (pintype "bidirectional"))
    )
    (net (code "148") (name "TDI") (class "Default")
      (node (ref "JTAG") (pin "3") (pinfunction "3_3") (pintype "passive"))
      (node (ref "U$1") (pin "97") (pinfunction "PJ.1/TDI/TCLK_97") (pintype "bidirectional"))
    )
    (net (code "149") (name "TDO") (class "Default")
      (node (ref "JTAG") (pin "1") (pinfunction "1_1") (pintype "passive"))
      (node (ref "U$1") (pin "96") (pinfunction "PJ.0/TDO_96") (pintype "bidirectional"))
    )
    (net (code "150") (name "TEST{slash}SBWTCK") (class "Default")
      (node (ref "JTAG") (pin "8") (pinfunction "8_8") (pintype "passive"))
      (node (ref "U$1") (pin "95") (pinfunction "TEST/SBWTCK_95") (pintype "bidirectional"))
    )
    (net (code "151") (name "TMS") (class "Default")
      (node (ref "JTAG") (pin "5") (pinfunction "5_5") (pintype "passive"))
      (node (ref "U$1") (pin "98") (pinfunction "PJ.2/TMS_98") (pintype "bidirectional"))
    )
    (net (code "152") (name "UART_CTS") (class "Default")
      (node (ref "JTAG") (pin "10") (pinfunction "10_10") (pintype "passive"))
    )
    (net (code "153") (name "UART_RTS") (class "Default")
      (node (ref "JTAG") (pin "13") (pinfunction "13_13") (pintype "passive"))
    )
    (net (code "154") (name "UART_RX") (class "Default")
      (node (ref "JTAG") (pin "14") (pinfunction "14_14") (pintype "passive"))
      (node (ref "P4") (pin "2") (pinfunction "2_2") (pintype "passive"))
      (node (ref "U$1") (pin "60") (pinfunction "P4.1_60") (pintype "bidirectional"))
    )
    (net (code "155") (name "UART_TX") (class "Default")
      (node (ref "JTAG") (pin "12") (pinfunction "12_12") (pintype "passive"))
      (node (ref "P4") (pin "3") (pinfunction "3_3") (pintype "passive"))
      (node (ref "U$1") (pin "61") (pinfunction "P4.2_61") (pintype "bidirectional"))
    )
    (net (code "156") (name "VASYS1{slash}2") (class "Default")
      (node (ref "C22") (pin "1") (pinfunction "1_1") (pintype "passive"))
      (node (ref "C23") (pin "1") (pinfunction "1_1") (pintype "passive"))
      (node (ref "C28") (pin "1") (pinfunction "1_1") (pintype "passive"))
      (node (ref "C32") (pin "1") (pinfunction "1_1") (pintype "passive"))
      (node (ref "U$1") (pin "20") (pinfunction "VASYS1_20") (pintype "bidirectional"))
      (node (ref "U$1") (pin "9") (pinfunction "VASYS2_9") (pintype "bidirectional"))
    )
    (net (code "157") (name "VCORE") (class "Default")
      (node (ref "C38") (pin "1") (pinfunction "1_1") (pintype "passive"))
      (node (ref "U$1") (pin "26") (pinfunction "VCORE_26") (pintype "bidirectional"))
    )
    (net (code "158") (name "VREF") (class "Default")
      (node (ref "C30") (pin "1") (pinfunction "1_1") (pintype "passive"))
      (node (ref "U$1") (pin "11") (pinfunction "VREF_11") (pintype "bidirectional"))
    )
    (net (code "159") (name "XIN") (class "Default")
      (node (ref "C100") (pin "1") (pinfunction "1_1") (pintype "passive"))
      (node (ref "U$1") (pin "27") (pinfunction "XIN_27") (pintype "bidirectional"))
      (node (ref "XT1") (pin "P2") (pinfunction "2_P2") (pintype "bidirectional"))
    )
    (net (code "160") (name "XOUT") (class "Default")
      (node (ref "C101") (pin "1") (pinfunction "1_1") (pintype "passive"))
      (node (ref "U$1") (pin "28") (pinfunction "XOUT_28") (pintype "bidirectional"))
      (node (ref "XT1") (pin "P1") (pinfunction "1_P1") (pintype "bidirectional"))
    )
    (net (code "161") (name "unconnected-(H11-NC1-Pad1)") (class "Default")
      (node (ref "H11") (pin "1") (pinfunction "NC1_1") (pintype "no_connect"))
    )
    (net (code "162") (name "unconnected-(H11-NC2-Pad5)") (class "Default")
      (node (ref "H11") (pin "5") (pinfunction "NC2_5") (pintype "no_connect"))
    )
    (net (code "163") (name "unconnected-(H11-NC3-Pad8)") (class "Default")
      (node (ref "H11") (pin "8") (pinfunction "NC3_8") (pintype "no_connect"))
    )
    (net (code "164") (name "unconnected-(H12-NC1-Pad1)") (class "Default")
      (node (ref "H12") (pin "1") (pinfunction "NC1_1") (pintype "no_connect"))
    )
    (net (code "165") (name "unconnected-(H12-NC2-Pad5)") (class "Default")
      (node (ref "H12") (pin "5") (pinfunction "NC2_5") (pintype "no_connect"))
    )
    (net (code "166") (name "unconnected-(H12-NC3-Pad8)") (class "Default")
      (node (ref "H12") (pin "8") (pinfunction "NC3_8") (pintype "no_connect"))
    )
    (net (code "167") (name "unconnected-(H21-NC1-Pad1)") (class "Default")
      (node (ref "H21") (pin "1") (pinfunction "NC1_1") (pintype "no_connect"))
    )
    (net (code "168") (name "unconnected-(H21-NC2-Pad5)") (class "Default")
      (node (ref "H21") (pin "5") (pinfunction "NC2_5") (pintype "no_connect"))
    )
    (net (code "169") (name "unconnected-(H21-NC3-Pad8)") (class "Default")
      (node (ref "H21") (pin "8") (pinfunction "NC3_8") (pintype "no_connect"))
    )
    (net (code "170") (name "unconnected-(H22-NC1-Pad1)") (class "Default")
      (node (ref "H22") (pin "1") (pinfunction "NC1_1") (pintype "no_connect"))
    )
    (net (code "171") (name "unconnected-(H22-NC2-Pad5)") (class "Default")
      (node (ref "H22") (pin "5") (pinfunction "NC2_5") (pintype "no_connect"))
    )
    (net (code "172") (name "unconnected-(H22-NC3-Pad8)") (class "Default")
      (node (ref "H22") (pin "8") (pinfunction "NC3_8") (pintype "no_connect"))
    )
    (net (code "173") (name "unconnected-(JTAG-Pad6)") (class "Default")
      (node (ref "JTAG") (pin "6") (pinfunction "6_6") (pintype "passive"))
    )
    (net (code "174") (name "unconnected-(N11-NC1-Pad1)") (class "Default")
      (node (ref "N11") (pin "1") (pinfunction "NC1_1") (pintype "no_connect"))
    )
    (net (code "175") (name "unconnected-(N11-NC2-Pad5)") (class "Default")
      (node (ref "N11") (pin "5") (pinfunction "NC2_5") (pintype "no_connect"))
    )
    (net (code "176") (name "unconnected-(N11-NC3-Pad8)") (class "Default")
      (node (ref "N11") (pin "8") (pinfunction "NC3_8") (pintype "no_connect"))
    )
    (net (code "177") (name "unconnected-(N12-NC1-Pad1)") (class "Default")
      (node (ref "N12") (pin "1") (pinfunction "NC1_1") (pintype "no_connect"))
    )
    (net (code "178") (name "unconnected-(N12-NC2-Pad5)") (class "Default")
      (node (ref "N12") (pin "5") (pinfunction "NC2_5") (pintype "no_connect"))
    )
    (net (code "179") (name "unconnected-(N12-NC3-Pad8)") (class "Default")
      (node (ref "N12") (pin "8") (pinfunction "NC3_8") (pintype "no_connect"))
    )
    (net (code "180") (name "unconnected-(N21-NC1-Pad1)") (class "Default")
      (node (ref "N21") (pin "1") (pinfunction "NC1_1") (pintype "no_connect"))
    )
    (net (code "181") (name "unconnected-(N21-NC2-Pad5)") (class "Default")
      (node (ref "N21") (pin "5") (pinfunction "NC2_5") (pintype "no_connect"))
    )
    (net (code "182") (name "unconnected-(N21-NC3-Pad8)") (class "Default")
      (node (ref "N21") (pin "8") (pinfunction "NC3_8") (pintype "no_connect"))
    )
    (net (code "183") (name "unconnected-(N22-NC1-Pad1)") (class "Default")
      (node (ref "N22") (pin "1") (pinfunction "NC1_1") (pintype "no_connect"))
    )
    (net (code "184") (name "unconnected-(N22-NC2-Pad5)") (class "Default")
      (node (ref "N22") (pin "5") (pinfunction "NC2_5") (pintype "no_connect"))
    )
    (net (code "185") (name "unconnected-(N22-NC3-Pad8)") (class "Default")
      (node (ref "N22") (pin "8") (pinfunction "NC3_8") (pintype "no_connect"))
    )
    (net (code "186") (name "unconnected-(R_INA1_VAR-E-Pad3)") (class "Default")
      (node (ref "R_INA1_VAR") (pin "3") (pinfunction "E_3") (pintype "passive"))
    )
    (net (code "187") (name "unconnected-(R_INA2_VAR-E-Pad3)") (class "Default")
      (node (ref "R_INA2_VAR") (pin "3") (pinfunction "E_3") (pintype "passive"))
    )
    (net (code "188") (name "unconnected-(SW1-Pad2)") (class "Default")
      (node (ref "SW1") (pin "2") (pinfunction "2_2") (pintype "passive"))
    )
    (net (code "189") (name "unconnected-(SW1-Pad3)") (class "Default")
      (node (ref "SW1") (pin "3") (pinfunction "3_3") (pintype "passive"))
    )
    (net (code "190") (name "unconnected-(SW2-Pad2)") (class "Default")
      (node (ref "SW2") (pin "2") (pinfunction "2_2") (pintype "passive"))
    )
    (net (code "191") (name "unconnected-(SW2-Pad3)") (class "Default")
      (node (ref "SW2") (pin "3") (pinfunction "3_3") (pintype "passive"))
    )
    (net (code "192") (name "unconnected-(SW3-Pad2)") (class "Default")
      (node (ref "SW3") (pin "2") (pinfunction "2_2") (pintype "passive"))
    )
    (net (code "193") (name "unconnected-(SW3-Pad3)") (class "Default")
      (node (ref "SW3") (pin "3") (pinfunction "3_3") (pintype "passive"))
    )
    (net (code "194") (name "unconnected-(SW4-Pad2)") (class "Default")
      (node (ref "SW4") (pin "2") (pinfunction "2_2") (pintype "passive"))
    )
    (net (code "195") (name "unconnected-(SW4-Pad3)") (class "Default")
      (node (ref "SW4") (pin "3") (pinfunction "3_3") (pintype "passive"))
    )
    (net (code "196") (name "unconnected-(SW5-Pad2)") (class "Default")
      (node (ref "SW5") (pin "2") (pinfunction "2_2") (pintype "passive"))
    )
    (net (code "197") (name "unconnected-(SW5-Pad3)") (class "Default")
      (node (ref "SW5") (pin "3") (pinfunction "3_3") (pintype "passive"))
    )
    (net (code "198") (name "unconnected-(T11-NC1-Pad1)") (class "Default")
      (node (ref "T11") (pin "1") (pinfunction "NC1_1") (pintype "no_connect"))
    )
    (net (code "199") (name "unconnected-(T11-NC2-Pad5)") (class "Default")
      (node (ref "T11") (pin "5") (pinfunction "NC2_5") (pintype "no_connect"))
    )
    (net (code "200") (name "unconnected-(T11-NC3-Pad8)") (class "Default")
      (node (ref "T11") (pin "8") (pinfunction "NC3_8") (pintype "no_connect"))
    )
    (net (code "201") (name "unconnected-(T12-NC1-Pad1)") (class "Default")
      (node (ref "T12") (pin "1") (pinfunction "NC1_1") (pintype "no_connect"))
    )
    (net (code "202") (name "unconnected-(T12-NC2-Pad5)") (class "Default")
      (node (ref "T12") (pin "5") (pinfunction "NC2_5") (pintype "no_connect"))
    )
    (net (code "203") (name "unconnected-(T12-NC3-Pad8)") (class "Default")
      (node (ref "T12") (pin "8") (pinfunction "NC3_8") (pintype "no_connect"))
    )
    (net (code "204") (name "unconnected-(T21-NC1-Pad1)") (class "Default")
      (node (ref "T21") (pin "1") (pinfunction "NC1_1") (pintype "no_connect"))
    )
    (net (code "205") (name "unconnected-(T21-NC2-Pad5)") (class "Default")
      (node (ref "T21") (pin "5") (pinfunction "NC2_5") (pintype "no_connect"))
    )
    (net (code "206") (name "unconnected-(T21-NC3-Pad8)") (class "Default")
      (node (ref "T21") (pin "8") (pinfunction "NC3_8") (pintype "no_connect"))
    )
    (net (code "207") (name "unconnected-(T22-NC1-Pad1)") (class "Default")
      (node (ref "T22") (pin "1") (pinfunction "NC1_1") (pintype "no_connect"))
    )
    (net (code "208") (name "unconnected-(T22-NC2-Pad5)") (class "Default")
      (node (ref "T22") (pin "5") (pinfunction "NC2_5") (pintype "no_connect"))
    )
    (net (code "209") (name "unconnected-(T22-NC3-Pad8)") (class "Default")
      (node (ref "T22") (pin "8") (pinfunction "NC3_8") (pintype "no_connect"))
    )
    (net (code "210") (name "unconnected-(U$1-P2.1-Pad43)") (class "Default")
      (node (ref "U$1") (pin "43") (pinfunction "P2.1_43") (pintype "bidirectional"))
    )
    (net (code "211") (name "unconnected-(U$1-P2.2-Pad44)") (class "Default")
      (node (ref "U$1") (pin "44") (pinfunction "P2.2_44") (pintype "bidirectional"))
    )
    (net (code "212") (name "unconnected-(U$1-P2.3-Pad45)") (class "Default")
      (node (ref "U$1") (pin "45") (pinfunction "P2.3_45") (pintype "bidirectional"))
    )
    (net (code "213") (name "unconnected-(U$1-P2.4-Pad47)") (class "Default")
      (node (ref "U$1") (pin "47") (pinfunction "P2.4_47") (pintype "bidirectional"))
    )
    (net (code "214") (name "unconnected-(U$1-P2.5-Pad48)") (class "Default")
      (node (ref "U$1") (pin "48") (pinfunction "P2.5_48") (pintype "bidirectional"))
    )
    (net (code "215") (name "unconnected-(U$1-P2.6-Pad49)") (class "Default")
      (node (ref "U$1") (pin "49") (pinfunction "P2.6_49") (pintype "bidirectional"))
    )
    (net (code "216") (name "unconnected-(U$1-P2.7-Pad50)") (class "Default")
      (node (ref "U$1") (pin "50") (pinfunction "P2.7_50") (pintype "bidirectional"))
    )
    (net (code "217") (name "unconnected-(U$1-P7.3-Pad88)") (class "Default")
      (node (ref "U$1") (pin "88") (pinfunction "P7.3_88") (pintype "bidirectional"))
    )
    (net (code "218") (name "unconnected-(U$1-P7.4-Pad89)") (class "Default")
      (node (ref "U$1") (pin "89") (pinfunction "P7.4_89") (pintype "bidirectional"))
    )
    (net (code "219") (name "unconnected-(U$1-P7.5-Pad90)") (class "Default")
      (node (ref "U$1") (pin "90") (pinfunction "P7.5_90") (pintype "bidirectional"))
    )
    (net (code "220") (name "unconnected-(U$1-P7.6-Pad91)") (class "Default")
      (node (ref "U$1") (pin "91") (pinfunction "P7.6_91") (pintype "bidirectional"))
    )
    (net (code "221") (name "unconnected-(U$1-P7.7-Pad92)") (class "Default")
      (node (ref "U$1") (pin "92") (pinfunction "P7.7_92") (pintype "bidirectional"))
    )
    (net (code "222") (name "unconnected-(U$1-P8.0-Pad93)") (class "Default")
      (node (ref "U$1") (pin "93") (pinfunction "P8.0_93") (pintype "bidirectional"))
    )
    (net (code "223") (name "unconnected-(U$1-RTCCAP0-Pad31)") (class "Default")
      (node (ref "U$1") (pin "31") (pinfunction "RTCCAP0_31") (pintype "bidirectional"))
    )
    (net (code "224") (name "unconnected-(U$1-RTCCAP1-Pad30)") (class "Default")
      (node (ref "U$1") (pin "30") (pinfunction "RTCCAP1_30") (pintype "bidirectional"))
    )
    (net (code "225") (name "unconnected-(X_LS-Pad3)") (class "Default")
      (node (ref "X_LS") (pin "3") (pinfunction "3_3") (pintype "bidirectional"))
    )
    (net (code "226") (name "unconnected-(X_LS-Pad4)") (class "Default")
      (node (ref "X_LS") (pin "4") (pinfunction "4_4") (pintype "bidirectional"))
    )
    (net (code "227") (name "unconnected-(X_RS-Pad3)") (class "Default")
      (node (ref "X_RS") (pin "3") (pinfunction "3_3") (pintype "bidirectional"))
    )
    (net (code "228") (name "unconnected-(X_RS-Pad4)") (class "Default")
      (node (ref "X_RS") (pin "4") (pinfunction "4_4") (pintype "bidirectional"))
    )
  )
)
